# range_cape.net
KiCad netlist of a schematic drawn in EAGLE
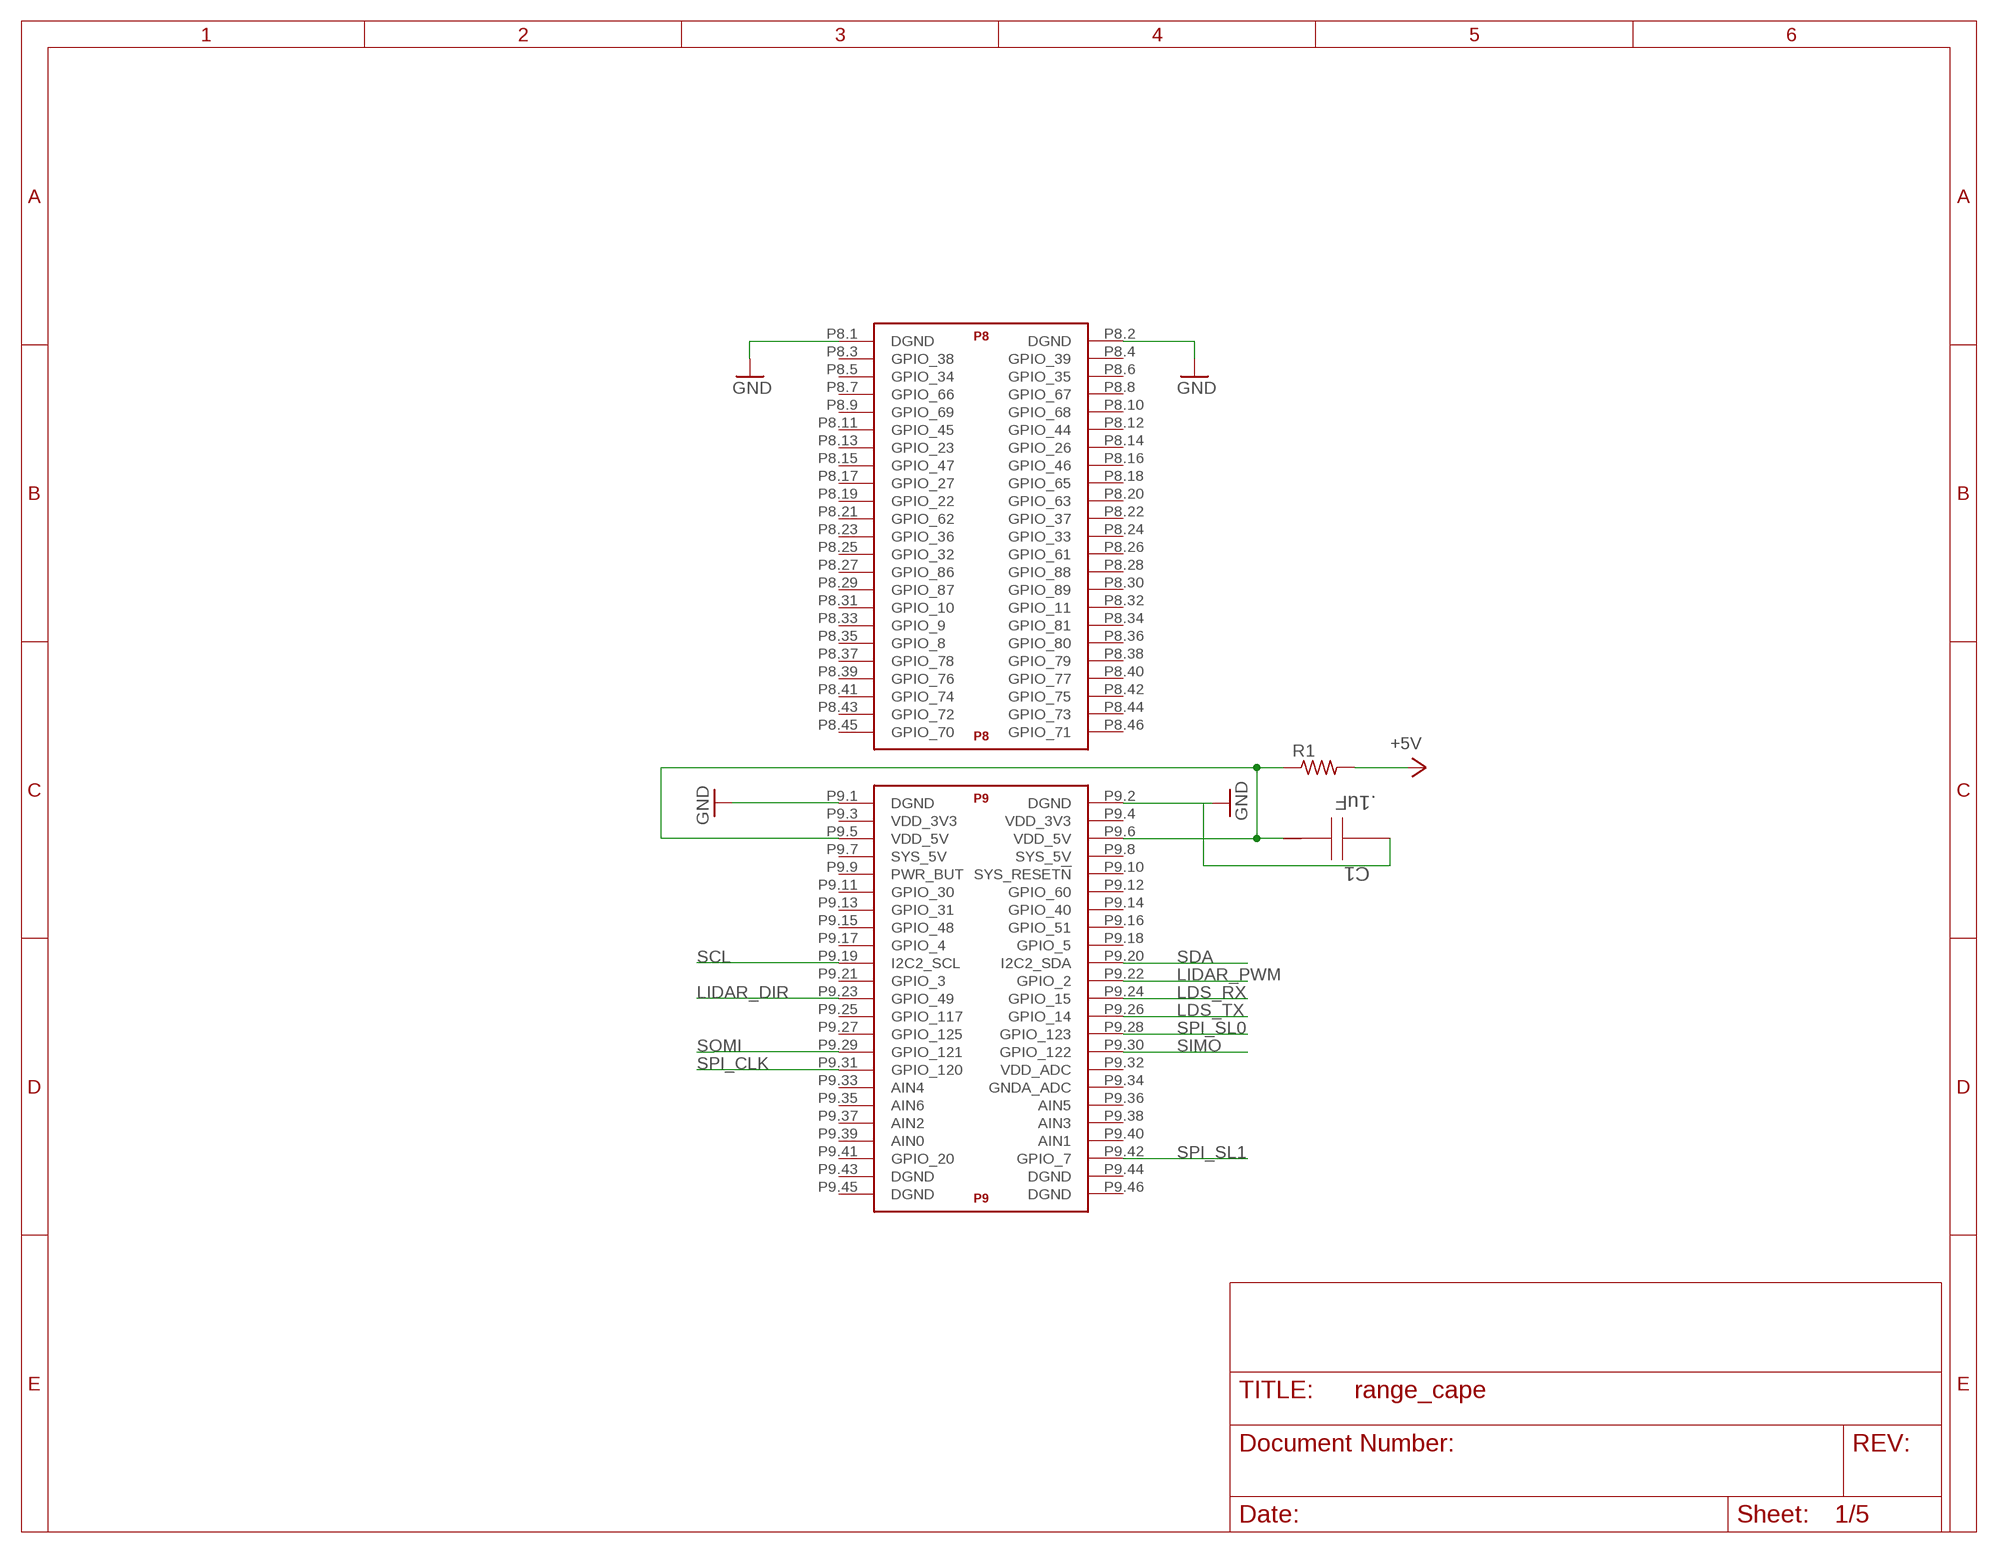
[diagram p0: schematic, sheet 1]
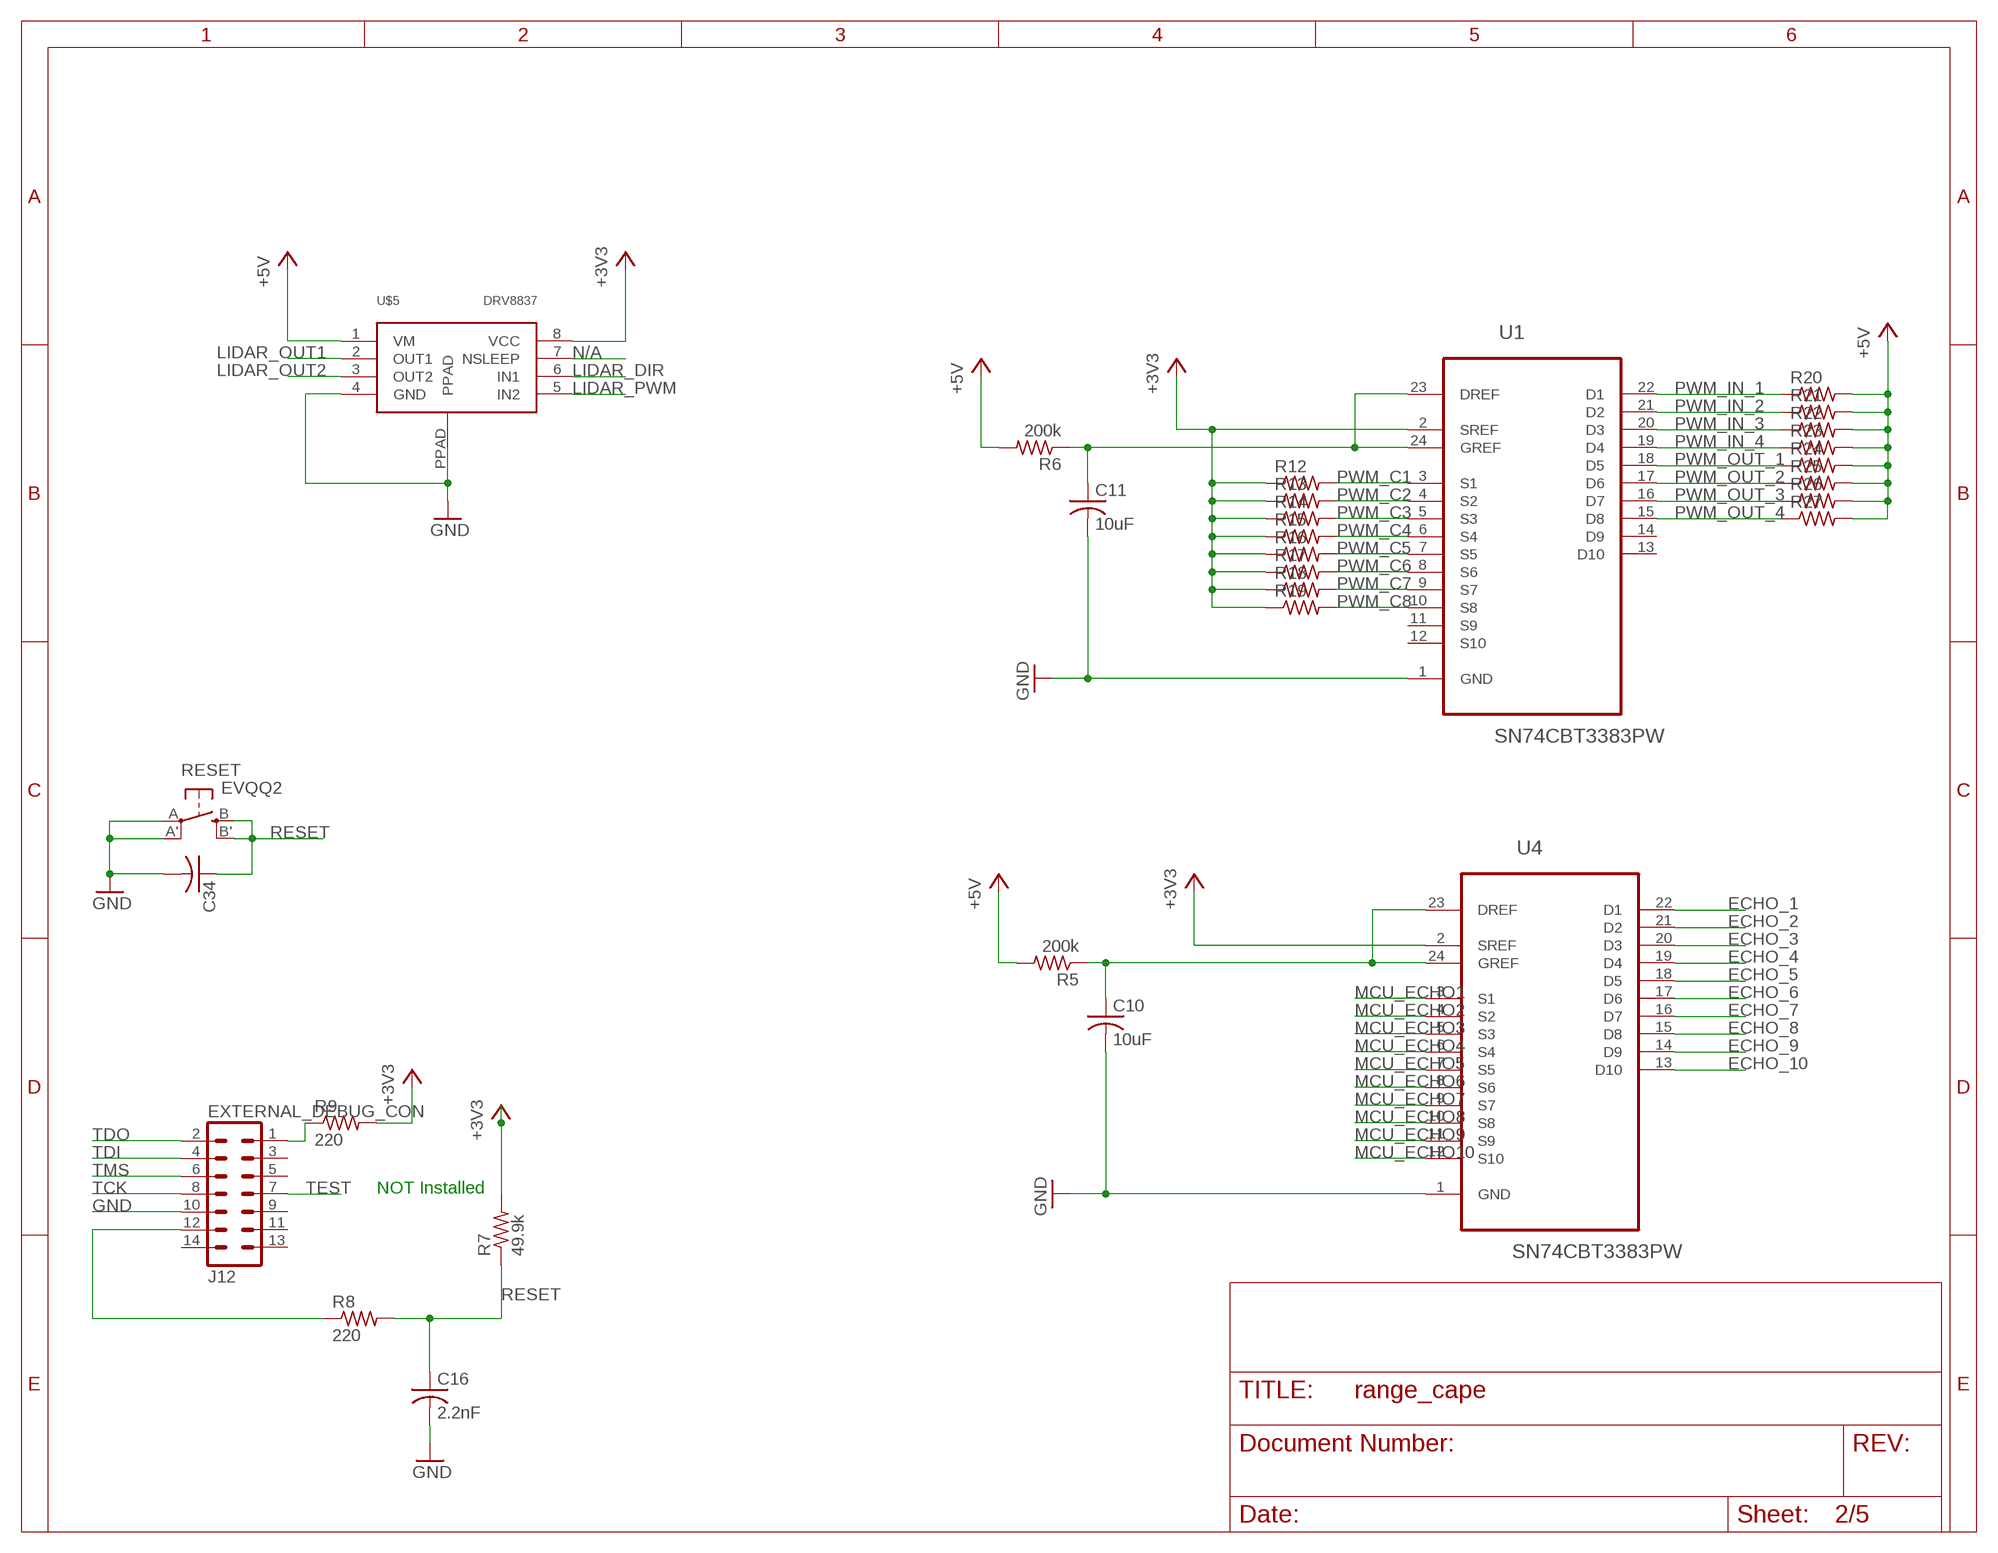
[diagram p1: schematic, sheet 2]
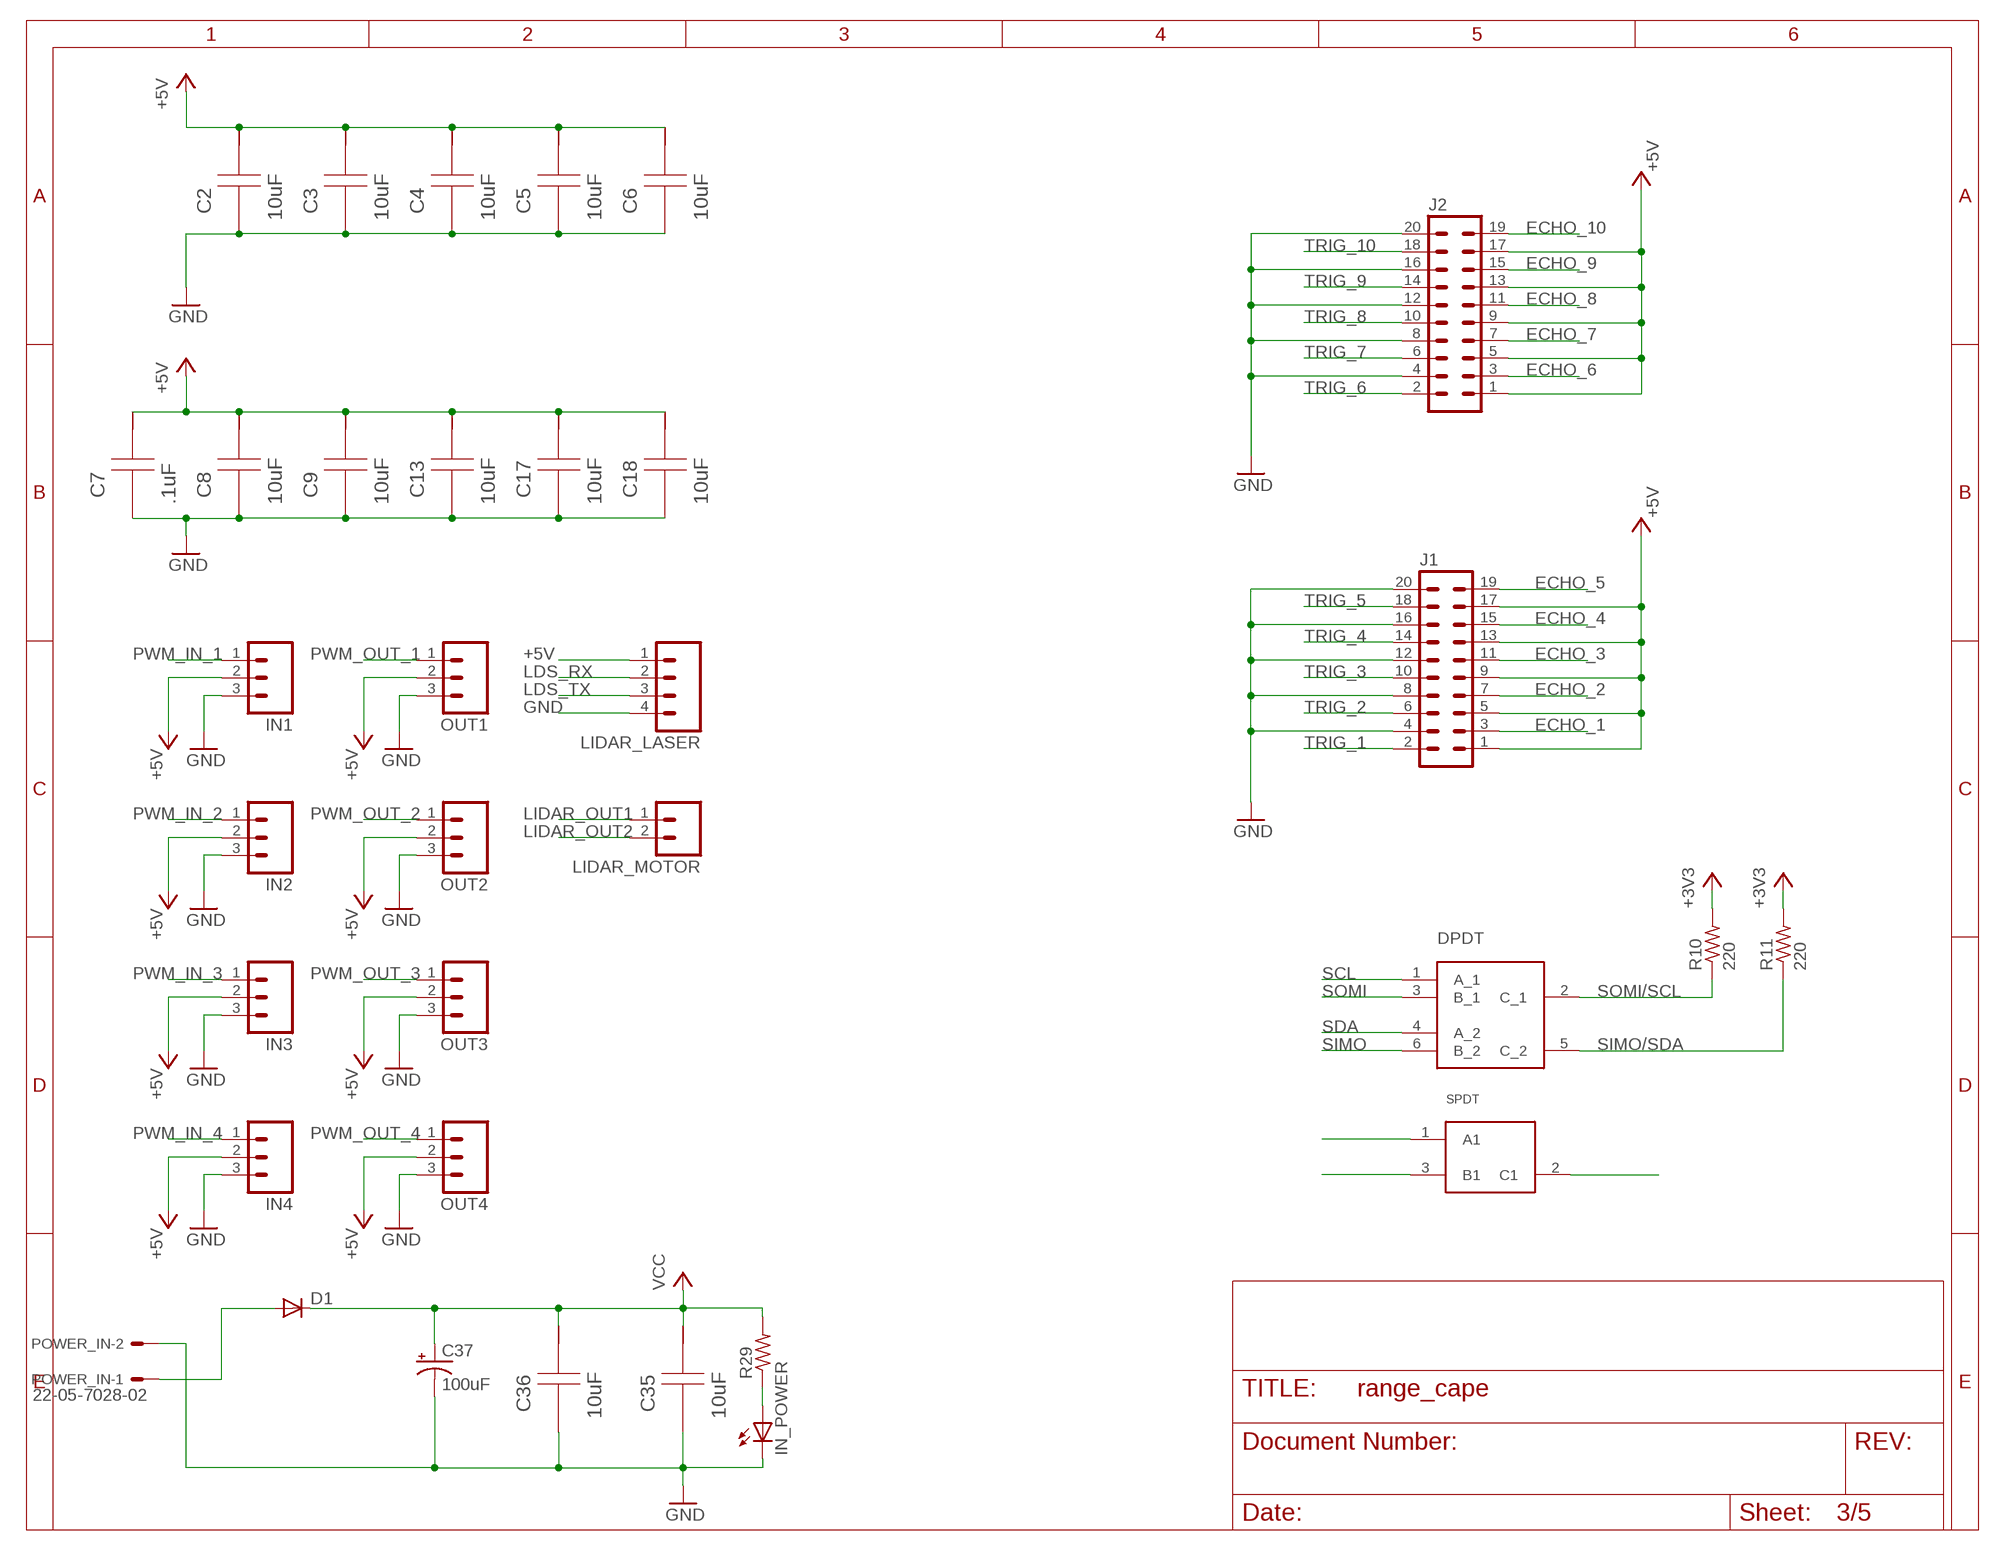
[diagram p2: schematic, sheet 3]
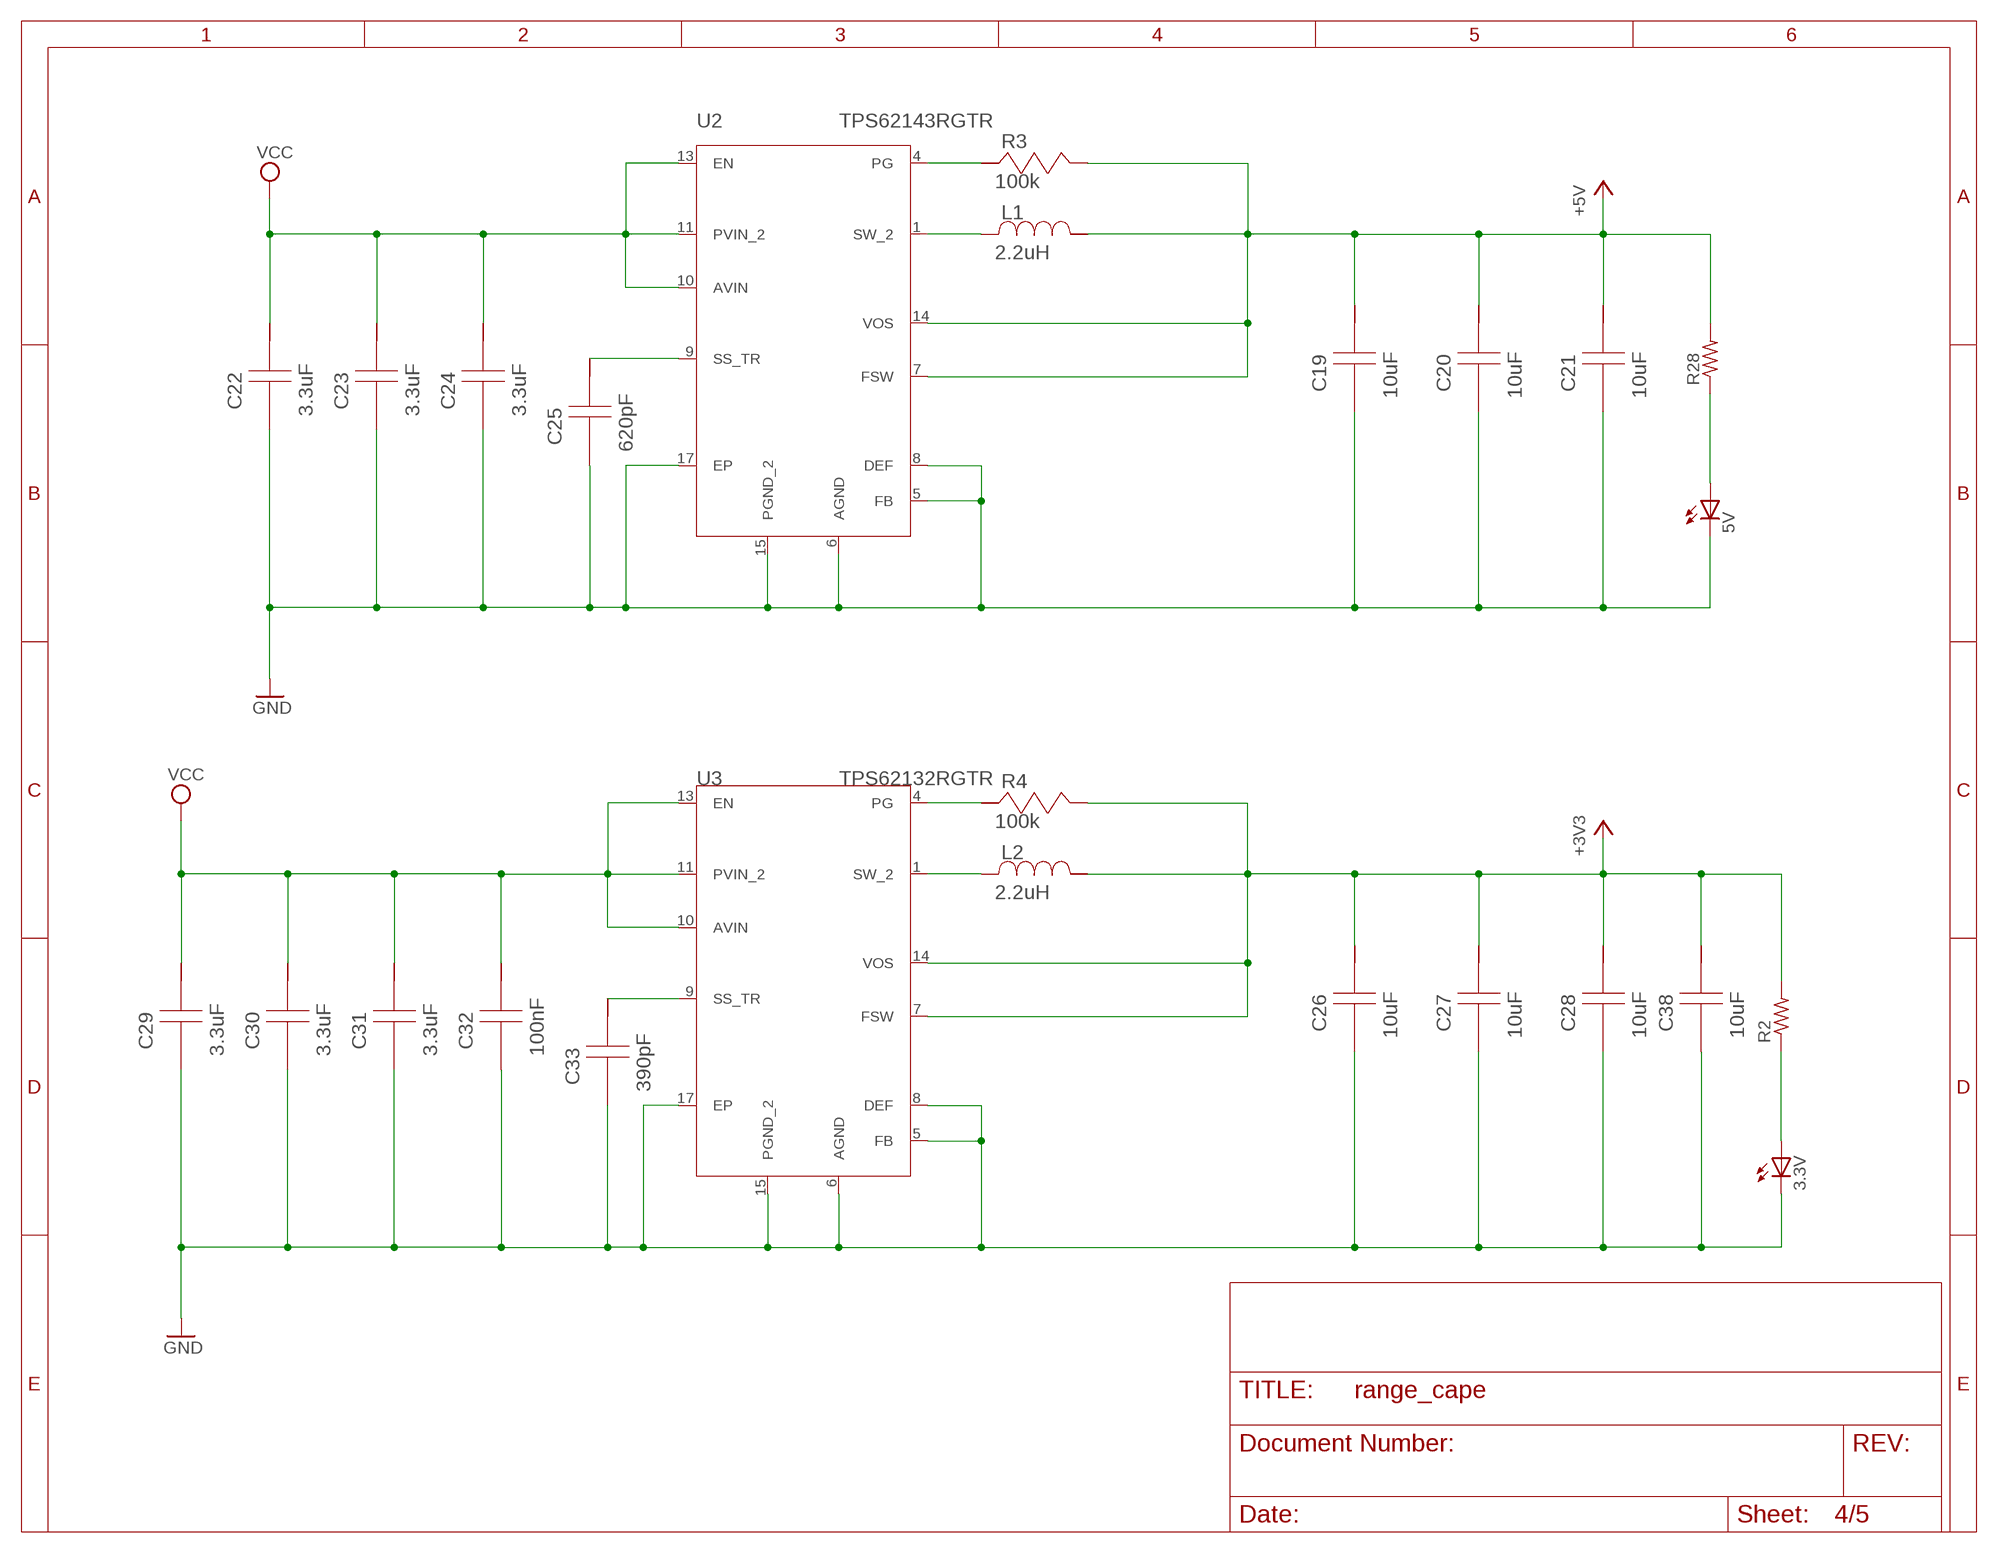
[diagram p3: schematic, sheet 4]
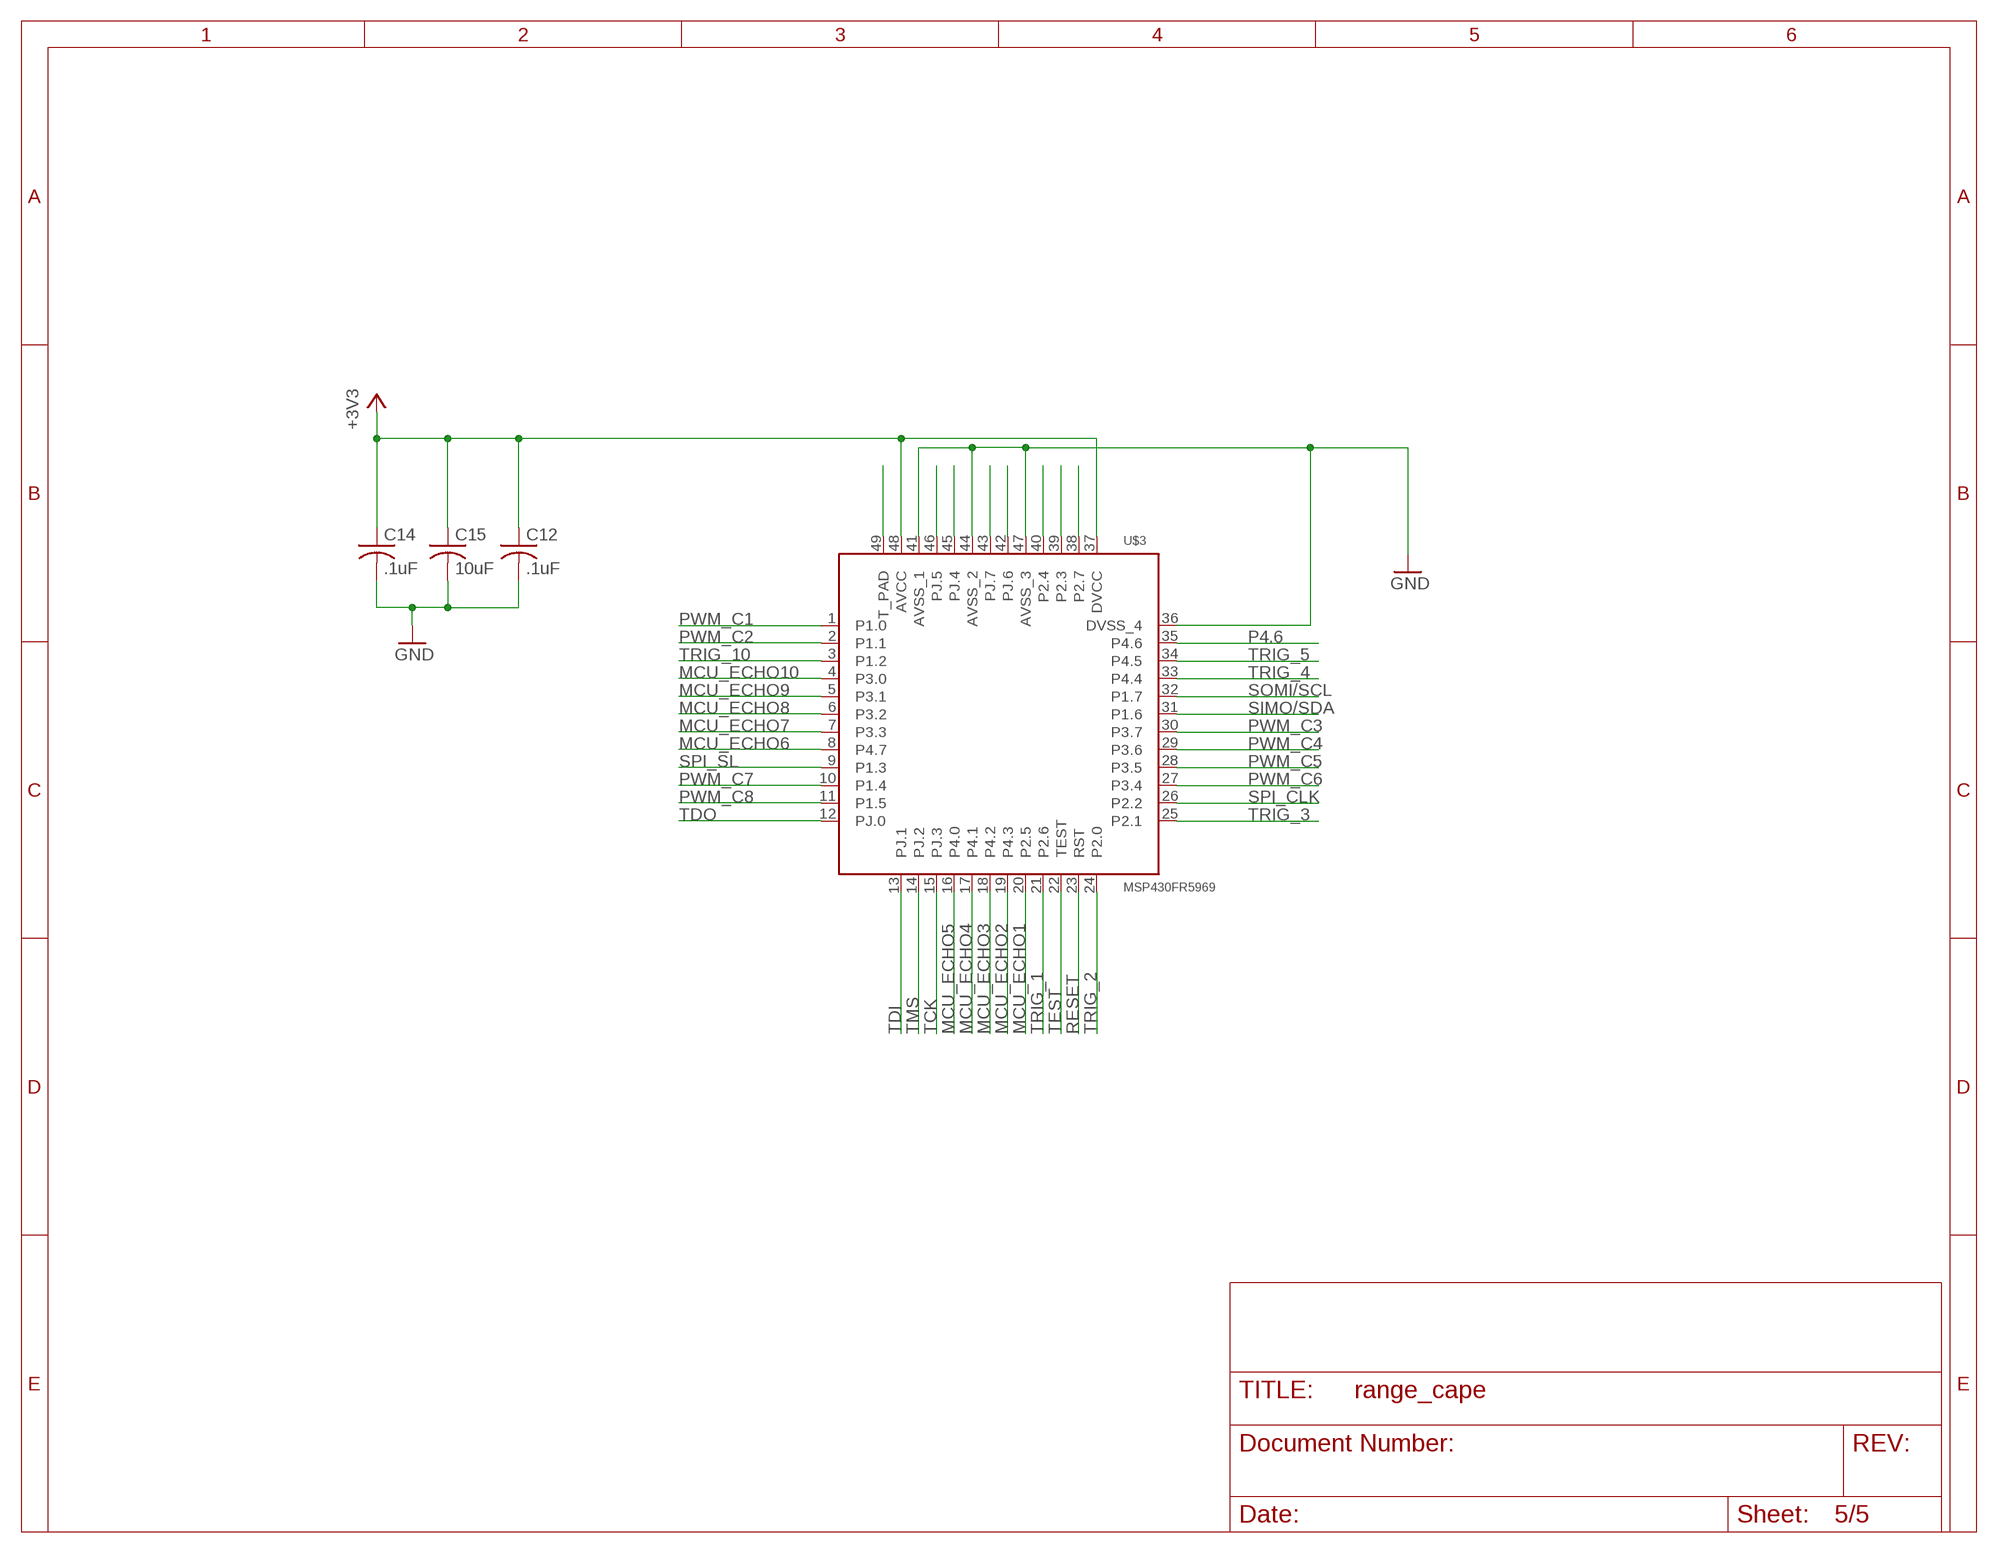
[diagram p4: schematic, sheet 5]

(export (version "E")
  (design (tool "Eeschema 10.0.6"))
  (components
    (comp (ref "C1")
      (value ".1uF")
      (footprint "eagle-import:1206")
      (fields (field (name "MANUFACTURER_PART_NUMBER") "C3216X5R1A106K"))
      (libsource (lib "eagle-import") (part "C3216X5R1A106K"))
    )
    (comp (ref "R1")
      (value "R-US_R1206")
      (footprint "eagle-import:R1206")
      (libsource (lib "eagle-import") (part "R-US_R1206"))
    )
    (comp (ref "U$1")
      (value "BEAGLE_BONE_BLACK_CAPE")
      (footprint "eagle-import:BEAGLE_BONE_BLACK_CAPE")
      (libsource (lib "eagle-import") (part "BEAGLE_BONE_BLACK_CAPE"))
    )
    (comp (ref "C10")
      (value "10uF")
      (footprint "eagle-import:C0805")
      (libsource (lib "eagle-import") (part "C-USC0805"))
    )
    (comp (ref "C11")
      (value "10uF")
      (footprint "eagle-import:C0805")
      (libsource (lib "eagle-import") (part "C-USC0805"))
    )
    (comp (ref "C16")
      (value "2.2nF")
      (footprint "eagle-import:C0603")
      (libsource (lib "eagle-import") (part "C-USC0603"))
    )
    (comp (ref "C34")
      (value "C-USC1206")
      (footprint "eagle-import:C1206")
      (libsource (lib "eagle-import") (part "C-USC1206"))
    )
    (comp (ref "J12")
      (value "EXTERNAL_DEBUG_CON")
      (footprint "eagle-import:EXTERNAL_DEBUG")
      (libsource (lib "eagle-import") (part "EXTERNAL_DEBUG_CON"))
    )
    (comp (ref "R5")
      (value "200k")
      (footprint "eagle-import:R0603")
      (libsource (lib "eagle-import") (part "R-US_R0603"))
    )
    (comp (ref "R6")
      (value "200k")
      (footprint "eagle-import:R0603")
      (libsource (lib "eagle-import") (part "R-US_R0603"))
    )
    (comp (ref "R7")
      (value "49.9k")
      (footprint "eagle-import:R0603")
      (libsource (lib "eagle-import") (part "R-US_R0603"))
    )
    (comp (ref "R8")
      (value "220")
      (footprint "eagle-import:R0603")
      (libsource (lib "eagle-import") (part "R-US_R0603"))
    )
    (comp (ref "R9")
      (value "220")
      (footprint "eagle-import:R0603")
      (libsource (lib "eagle-import") (part "R-US_R0603"))
    )
    (comp (ref "R12")
      (value "R-US_R0402")
      (footprint "eagle-import:R0402")
      (libsource (lib "eagle-import") (part "R-US_R0402"))
    )
    (comp (ref "R13")
      (value "R-US_R0402")
      (footprint "eagle-import:R0402")
      (libsource (lib "eagle-import") (part "R-US_R0402"))
    )
    (comp (ref "R14")
      (value "R-US_R0402")
      (footprint "eagle-import:R0402")
      (libsource (lib "eagle-import") (part "R-US_R0402"))
    )
    (comp (ref "R15")
      (value "R-US_R0402")
      (footprint "eagle-import:R0402")
      (libsource (lib "eagle-import") (part "R-US_R0402"))
    )
    (comp (ref "R16")
      (value "R-US_R0402")
      (footprint "eagle-import:R0402")
      (libsource (lib "eagle-import") (part "R-US_R0402"))
    )
    (comp (ref "R17")
      (value "R-US_R0402")
      (footprint "eagle-import:R0402")
      (libsource (lib "eagle-import") (part "R-US_R0402"))
    )
    (comp (ref "R18")
      (value "R-US_R0402")
      (footprint "eagle-import:R0402")
      (libsource (lib "eagle-import") (part "R-US_R0402"))
    )
    (comp (ref "R19")
      (value "R-US_R0402")
      (footprint "eagle-import:R0402")
      (libsource (lib "eagle-import") (part "R-US_R0402"))
    )
    (comp (ref "R20")
      (value "R-US_R0402")
      (footprint "eagle-import:R0402")
      (libsource (lib "eagle-import") (part "R-US_R0402"))
    )
    (comp (ref "R21")
      (value "R-US_R0402")
      (footprint "eagle-import:R0402")
      (libsource (lib "eagle-import") (part "R-US_R0402"))
    )
    (comp (ref "R22")
      (value "R-US_R0402")
      (footprint "eagle-import:R0402")
      (libsource (lib "eagle-import") (part "R-US_R0402"))
    )
    (comp (ref "R23")
      (value "R-US_R0402")
      (footprint "eagle-import:R0402")
      (libsource (lib "eagle-import") (part "R-US_R0402"))
    )
    (comp (ref "R24")
      (value "R-US_R0402")
      (footprint "eagle-import:R0402")
      (libsource (lib "eagle-import") (part "R-US_R0402"))
    )
    (comp (ref "R25")
      (value "R-US_R0402")
      (footprint "eagle-import:R0402")
      (libsource (lib "eagle-import") (part "R-US_R0402"))
    )
    (comp (ref "R26")
      (value "R-US_R0402")
      (footprint "eagle-import:R0402")
      (libsource (lib "eagle-import") (part "R-US_R0402"))
    )
    (comp (ref "R27")
      (value "R-US_R0402")
      (footprint "eagle-import:R0402")
      (libsource (lib "eagle-import") (part "R-US_R0402"))
    )
    (comp (ref "RESET")
      (value "EVQQ2")
      (footprint "eagle-import:EVQ-Q2")
      (libsource (lib "eagle-import") (part "EVQQ2"))
    )
    (comp (ref "U$5")
      (value "DRV8837")
      (footprint "eagle-import:WSON-8")
      (libsource (lib "eagle-import") (part "DRV8837"))
    )
    (comp (ref "U1")
      (value "SN74CBT3383PW")
      (footprint "eagle-import:SOP65P640X120-24N")
      (libsource (lib "eagle-import") (part "SN74CBT3383PW"))
    )
    (comp (ref "U4")
      (value "SN74CBT3383PW")
      (footprint "eagle-import:SOP65P640X120-24N")
      (libsource (lib "eagle-import") (part "SN74CBT3383PW"))
    )
    (comp (ref "C12")
      (value ".1uF")
      (footprint "eagle-import:C0805")
      (libsource (lib "eagle-import") (part "C-USC0805"))
    )
    (comp (ref "C14")
      (value ".1uF")
      (footprint "eagle-import:C0805")
      (libsource (lib "eagle-import") (part "C-USC0805"))
    )
    (comp (ref "C15")
      (value "10uF")
      (footprint "eagle-import:C0805")
      (libsource (lib "eagle-import") (part "C-USC0805"))
    )
    (comp (ref "U$3")
      (value "MSP430FR5969")
      (footprint "eagle-import:QFN50P700X700X100-49N")
      (libsource (lib "eagle-import") (part "MSP430FR5969"))
    )
    (comp (ref "C2")
      (value "10uF")
      (footprint "eagle-import:1206")
      (fields (field (name "MANUFACTURER_PART_NUMBER") "C3216X5R1A106K"))
      (libsource (lib "eagle-import") (part "C3216X5R1A106K"))
    )
    (comp (ref "C3")
      (value "10uF")
      (footprint "eagle-import:1206")
      (fields (field (name "MANUFACTURER_PART_NUMBER") "C3216X5R1A106K"))
      (libsource (lib "eagle-import") (part "C3216X5R1A106K"))
    )
    (comp (ref "C4")
      (value "10uF")
      (footprint "eagle-import:1206")
      (fields (field (name "MANUFACTURER_PART_NUMBER") "C3216X5R1A106K"))
      (libsource (lib "eagle-import") (part "C3216X5R1A106K"))
    )
    (comp (ref "C5")
      (value "10uF")
      (footprint "eagle-import:1206")
      (fields (field (name "MANUFACTURER_PART_NUMBER") "C3216X5R1A106K"))
      (libsource (lib "eagle-import") (part "C3216X5R1A106K"))
    )
    (comp (ref "C6")
      (value "10uF")
      (footprint "eagle-import:1206")
      (fields (field (name "MANUFACTURER_PART_NUMBER") "C3216X5R1A106K"))
      (libsource (lib "eagle-import") (part "C3216X5R1A106K"))
    )
    (comp (ref "C7")
      (value ".1uF")
      (footprint "eagle-import:1206")
      (fields (field (name "MANUFACTURER_PART_NUMBER") "C3216X5R1A106K"))
      (libsource (lib "eagle-import") (part "C3216X5R1A106K"))
    )
    (comp (ref "C8")
      (value "10uF")
      (footprint "eagle-import:1206")
      (fields (field (name "MANUFACTURER_PART_NUMBER") "C3216X5R1A106K"))
      (libsource (lib "eagle-import") (part "C3216X5R1A106K"))
    )
    (comp (ref "C9")
      (value "10uF")
      (footprint "eagle-import:1206")
      (fields (field (name "MANUFACTURER_PART_NUMBER") "C3216X5R1A106K"))
      (libsource (lib "eagle-import") (part "C3216X5R1A106K"))
    )
    (comp (ref "C13")
      (value "10uF")
      (footprint "eagle-import:1206")
      (fields (field (name "MANUFACTURER_PART_NUMBER") "C3216X5R1A106K"))
      (libsource (lib "eagle-import") (part "C3216X5R1A106K"))
    )
    (comp (ref "C17")
      (value "10uF")
      (footprint "eagle-import:1206")
      (fields (field (name "MANUFACTURER_PART_NUMBER") "C3216X5R1A106K"))
      (libsource (lib "eagle-import") (part "C3216X5R1A106K"))
    )
    (comp (ref "C18")
      (value "10uF")
      (footprint "eagle-import:1206")
      (fields (field (name "MANUFACTURER_PART_NUMBER") "C3216X5R1A106K"))
      (libsource (lib "eagle-import") (part "C3216X5R1A106K"))
    )
    (comp (ref "C35")
      (value "10uF")
      (footprint "eagle-import:1206")
      (fields (field (name "MANUFACTURER_PART_NUMBER") "C3216X5R1A106K"))
      (libsource (lib "eagle-import") (part "C3216X5R1A106K"))
    )
    (comp (ref "C36")
      (value "10uF")
      (footprint "eagle-import:1206")
      (fields (field (name "MANUFACTURER_PART_NUMBER") "C3216X5R1A106K"))
      (libsource (lib "eagle-import") (part "C3216X5R1A106K"))
    )
    (comp (ref "C37")
      (value "100uF")
      (footprint "eagle-import:EIA7343")
      (libsource (lib "eagle-import") (part "100UF-10V-10%(TANT)"))
    )
    (comp (ref "D1")
      (value "DIODE-DO-214AC")
      (footprint "eagle-import:DO-214AC")
      (libsource (lib "eagle-import") (part "DIODE-DO-214AC"))
    )
    (comp (ref "IN1")
      (value "M03LOCK")
      (footprint "eagle-import:1X03_LOCK")
      (libsource (lib "eagle-import") (part "M03LOCK"))
    )
    (comp (ref "IN2")
      (value "M03LOCK")
      (footprint "eagle-import:1X03_LOCK")
      (libsource (lib "eagle-import") (part "M03LOCK"))
    )
    (comp (ref "IN3")
      (value "M03LOCK")
      (footprint "eagle-import:1X03_LOCK")
      (libsource (lib "eagle-import") (part "M03LOCK"))
    )
    (comp (ref "IN4")
      (value "M03LOCK")
      (footprint "eagle-import:1X03_LOCK")
      (libsource (lib "eagle-import") (part "M03LOCK"))
    )
    (comp (ref "IN_POWER")
      (value "LED_ESML0603")
      (footprint "eagle-import:LED_SML0603")
      (libsource (lib "eagle-import") (part "LED_ESML0603"))
    )
    (comp (ref "J1")
      (value "MA10-2")
      (footprint "eagle-import:MA10-2")
      (libsource (lib "eagle-import") (part "MA10-2"))
    )
    (comp (ref "J2")
      (value "MA10-2")
      (footprint "eagle-import:MA10-2")
      (libsource (lib "eagle-import") (part "MA10-2"))
    )
    (comp (ref "LIDAR_LASER")
      (value "M04JST-PTH-VERT")
      (footprint "eagle-import:JST-4-PTH-VERT")
      (libsource (lib "eagle-import") (part "M04JST-PTH-VERT"))
    )
    (comp (ref "LIDAR_MOTOR")
      (value "M02JST-PTH-VERT")
      (footprint "eagle-import:JST-2-PTH-VERT")
      (libsource (lib "eagle-import") (part "M02JST-PTH-VERT"))
    )
    (comp (ref "OUT1")
      (value "M03LOCK")
      (footprint "eagle-import:1X03_LOCK")
      (libsource (lib "eagle-import") (part "M03LOCK"))
    )
    (comp (ref "OUT2")
      (value "M03LOCK")
      (footprint "eagle-import:1X03_LOCK")
      (libsource (lib "eagle-import") (part "M03LOCK"))
    )
    (comp (ref "OUT3")
      (value "M03LOCK")
      (footprint "eagle-import:1X03_LOCK")
      (libsource (lib "eagle-import") (part "M03LOCK"))
    )
    (comp (ref "OUT4")
      (value "M03LOCK")
      (footprint "eagle-import:1X03_LOCK")
      (libsource (lib "eagle-import") (part "M03LOCK"))
    )
    (comp (ref "POWER_IN")
      (value "22-05-7028-02")
      (footprint "eagle-import:7395-02")
      (libsource (lib "eagle-import") (part "22-?-0205-7028"))
    )
    (comp (ref "R10")
      (value "220")
      (footprint "eagle-import:R0402")
      (libsource (lib "eagle-import") (part "R-US_R0402"))
    )
    (comp (ref "R11")
      (value "220")
      (footprint "eagle-import:R0402")
      (libsource (lib "eagle-import") (part "R-US_R0402"))
    )
    (comp (ref "R29")
      (value "R-US_R0603")
      (footprint "eagle-import:R0603")
      (libsource (lib "eagle-import") (part "R-US_R0603"))
    )
    (comp (ref "SPDT")
      (value "SPDT_SWITCH")
      (footprint "eagle-import:SPDT")
      (libsource (lib "eagle-import") (part "SPDT_SWITCH"))
    )
    (comp (ref "U$4")
      (value "DPDT_I2C_SPI")
      (footprint "eagle-import:DPDT")
      (libsource (lib "eagle-import") (part "DPDT_I2C_SPI"))
    )
    (comp (ref "3.3V")
      (value "LED_ESML0603")
      (footprint "eagle-import:LED_SML0603")
      (libsource (lib "eagle-import") (part "LED_ESML0603"))
    )
    (comp (ref "5V")
      (value "LED_ESML0603")
      (footprint "eagle-import:LED_SML0603")
      (libsource (lib "eagle-import") (part "LED_ESML0603"))
    )
    (comp (ref "C19")
      (value "10uF")
      (footprint "eagle-import:1206")
      (fields (field (name "MANUFACTURER_PART_NUMBER") "C3216X5R1A106K"))
      (libsource (lib "eagle-import") (part "5v_fixed_C3216X5R1A106K"))
    )
    (comp (ref "C20")
      (value "10uF")
      (footprint "eagle-import:1206")
      (fields (field (name "MANUFACTURER_PART_NUMBER") "C3216X5R1A106K"))
      (libsource (lib "eagle-import") (part "5v_fixed_C3216X5R1A106K"))
    )
    (comp (ref "C21")
      (value "10uF")
      (footprint "eagle-import:1206")
      (fields (field (name "MANUFACTURER_PART_NUMBER") "C3216X5R1A106K"))
      (libsource (lib "eagle-import") (part "5v_fixed_C3216X5R1A106K"))
    )
    (comp (ref "C22")
      (value "3.3uF")
      (footprint "eagle-import:C3216X7R1E335K")
      (fields (field (name "MANUFACTURER_PART_NUMBER") "C3216X7R1E335K"))
      (libsource (lib "eagle-import") (part "C3216X7R1E335K"))
    )
    (comp (ref "C23")
      (value "3.3uF")
      (footprint "eagle-import:C3216X7R1E335K")
      (fields (field (name "MANUFACTURER_PART_NUMBER") "C3216X7R1E335K"))
      (libsource (lib "eagle-import") (part "C3216X7R1E335K"))
    )
    (comp (ref "C24")
      (value "3.3uF")
      (footprint "eagle-import:C3216X7R1E335K")
      (fields (field (name "MANUFACTURER_PART_NUMBER") "C3216X7R1E335K"))
      (libsource (lib "eagle-import") (part "C3216X7R1E335K"))
    )
    (comp (ref "C25")
      (value "620pF")
      (footprint "eagle-import:0402")
      (fields (field (name "MANUFACTURER_PART_NUMBER") "GRM1555C1E621JA01D"))
      (libsource (lib "eagle-import") (part "GRM1555C1E621JA01D"))
    )
    (comp (ref "C26")
      (value "10uF")
      (footprint "eagle-import:1206")
      (fields (field (name "MANUFACTURER_PART_NUMBER") "C3216X5R1A106K"))
      (libsource (lib "eagle-import") (part "5v_fixed_C3216X5R1A106K"))
    )
    (comp (ref "C27")
      (value "10uF")
      (footprint "eagle-import:1206")
      (fields (field (name "MANUFACTURER_PART_NUMBER") "C3216X5R1A106K"))
      (libsource (lib "eagle-import") (part "5v_fixed_C3216X5R1A106K"))
    )
    (comp (ref "C28")
      (value "10uF")
      (footprint "eagle-import:1206")
      (fields (field (name "MANUFACTURER_PART_NUMBER") "C3216X5R1A106K"))
      (libsource (lib "eagle-import") (part "5v_fixed_C3216X5R1A106K"))
    )
    (comp (ref "C29")
      (value "3.3uF")
      (footprint "eagle-import:C3216X7R1E335K")
      (fields (field (name "MANUFACTURER_PART_NUMBER") "C3216X7R1E335K"))
      (libsource (lib "eagle-import") (part "C3216X7R1E335K"))
    )
    (comp (ref "C30")
      (value "3.3uF")
      (footprint "eagle-import:C3216X7R1E335K")
      (fields (field (name "MANUFACTURER_PART_NUMBER") "C3216X7R1E335K"))
      (libsource (lib "eagle-import") (part "C3216X7R1E335K"))
    )
    (comp (ref "C31")
      (value "3.3uF")
      (footprint "eagle-import:C3216X7R1E335K")
      (fields (field (name "MANUFACTURER_PART_NUMBER") "C3216X7R1E335K"))
      (libsource (lib "eagle-import") (part "C3216X7R1E335K"))
    )
    (comp (ref "C32")
      (value "100nF")
      (footprint "eagle-import:0603")
      (fields (field (name "MANUFACTURER_PART_NUMBER") "C0603C104K3RACTU"))
      (libsource (lib "eagle-import") (part "C0603C104K3RACTU"))
    )
    (comp (ref "C33")
      (value "390pF")
      (footprint "eagle-import:0805")
      (fields (field (name "MANUFACTURER_PART_NUMBER") "08055C391KAT2A"))
      (libsource (lib "eagle-import") (part "08055C391KAT2A"))
    )
    (comp (ref "C38")
      (value "10uF")
      (footprint "eagle-import:1206")
      (fields (field (name "MANUFACTURER_PART_NUMBER") "C3216X5R1A106K"))
      (libsource (lib "eagle-import") (part "5v_fixed_C3216X5R1A106K"))
    )
    (comp (ref "L1")
      (value "2.2uH")
      (footprint "eagle-import:IHLP-1212BZ")
      (fields
        (field (name "MANUFACTURER") "Vishay")
        (field (name "MANUFACTURER_PART_NUMBER") "IHLP1212BZER2R2M11")
      )
      (libsource (lib "eagle-import") (part "IHLP1212BZER2R2M11"))
    )
    (comp (ref "L2")
      (value "2.2uH")
      (footprint "eagle-import:IHLP-1212BZ")
      (fields
        (field (name "MANUFACTURER") "Vishay")
        (field (name "MANUFACTURER_PART_NUMBER") "IHLP1212BZER2R2M11")
      )
      (libsource (lib "eagle-import") (part "IHLP1212BZER2R2M11"))
    )
    (comp (ref "R2")
      (value "R-US_R0603")
      (footprint "eagle-import:R0603")
      (libsource (lib "eagle-import") (part "R-US_R0603"))
    )
    (comp (ref "R3")
      (value "100k")
      (footprint "eagle-import:CRCW0402100KFKED")
      (fields
        (field (name "MANUFACTURER_PART_NUMBER") "CRCW0402100KFKED")
        (field (name "POWER") "0.063")
        (field (name "TOLERANCE") "1.0")
      )
      (libsource (lib "eagle-import") (part "CRCW0402100KFKED"))
    )
    (comp (ref "R4")
      (value "100k")
      (footprint "eagle-import:CRCW0402100KFKED")
      (fields
        (field (name "MANUFACTURER_PART_NUMBER") "CRCW0402100KFKED")
        (field (name "POWER") "0.063")
        (field (name "TOLERANCE") "1.0")
      )
      (libsource (lib "eagle-import") (part "CRCW0402100KFKED"))
    )
    (comp (ref "R28")
      (value "R-US_R0603")
      (footprint "eagle-import:R0603")
      (libsource (lib "eagle-import") (part "R-US_R0603"))
    )
    (comp (ref "U2")
      (value "TPS62143RGTR")
      (footprint "eagle-import:S-PVQFN-N16")
      (fields (field (name "MANUFACTURER_PART_NUMBER") "TPS62131RGTR"))
      (libsource (lib "eagle-import") (part "TPS62143RGTR"))
    )
    (comp (ref "U3")
      (value "TPS62132RGTR")
      (footprint "eagle-import:S-PVQFN-N16")
      (fields (field (name "MANUFACTURER_PART_NUMBER") "TPS62131RGTR"))
      (libsource (lib "eagle-import") (part "TPS62132RGTR"))
    )
  )
  (nets
    (net (code "1") (name "+3V3") (class "Default")
      (node (ref "C12") (pin "1") (pinfunction "1_1") (pintype "passive"))
      (node (ref "C14") (pin "1") (pinfunction "1_1") (pintype "passive"))
      (node (ref "C15") (pin "1") (pinfunction "1_1") (pintype "passive"))
      (node (ref "C26") (pin "1") (pinfunction "1_1") (pintype "passive"))
      (node (ref "C27") (pin "1") (pinfunction "1_1") (pintype "passive"))
      (node (ref "C28") (pin "1") (pinfunction "1_1") (pintype "passive"))
      (node (ref "C38") (pin "1") (pinfunction "1_1") (pintype "passive"))
      (node (ref "L2") (pin "2") (pinfunction "2_2") (pintype "passive"))
      (node (ref "R10") (pin "2") (pinfunction "2_2") (pintype "passive"))
      (node (ref "R11") (pin "2") (pinfunction "2_2") (pintype "passive"))
      (node (ref "R12") (pin "1") (pinfunction "1_1") (pintype "passive"))
      (node (ref "R13") (pin "1") (pinfunction "1_1") (pintype "passive"))
      (node (ref "R14") (pin "1") (pinfunction "1_1") (pintype "passive"))
      (node (ref "R15") (pin "1") (pinfunction "1_1") (pintype "passive"))
      (node (ref "R16") (pin "1") (pinfunction "1_1") (pintype "passive"))
      (node (ref "R17") (pin "1") (pinfunction "1_1") (pintype "passive"))
      (node (ref "R18") (pin "1") (pinfunction "1_1") (pintype "passive"))
      (node (ref "R19") (pin "1") (pinfunction "1_1") (pintype "passive"))
      (node (ref "R2") (pin "2") (pinfunction "2_2") (pintype "passive"))
      (node (ref "R4") (pin "1") (pinfunction "1_1") (pintype "passive"))
      (node (ref "R7") (pin "2") (pinfunction "2_2") (pintype "passive"))
      (node (ref "R9") (pin "2") (pinfunction "2_2") (pintype "passive"))
      (node (ref "U$3") (pin "37") (pinfunction "DVCC_37") (pintype "power_in"))
      (node (ref "U$3") (pin "48") (pinfunction "AVCC_48") (pintype "power_in"))
      (node (ref "U$5") (pin "8") (pinfunction "VCC_8") (pintype "bidirectional"))
      (node (ref "U1") (pin "2") (pinfunction "SREF_2") (pintype "input"))
      (node (ref "U3") (pin "14") (pinfunction "VOS_14") (pintype "passive"))
      (node (ref "U3") (pin "7") (pinfunction "FSW_7") (pintype "passive"))
      (node (ref "U4") (pin "2") (pinfunction "SREF_2") (pintype "input"))
    )
    (net (code "2") (name "+5V") (class "Default")
      (node (ref "C13") (pin "1") (pinfunction "1_1") (pintype "passive"))
      (node (ref "C17") (pin "1") (pinfunction "1_1") (pintype "passive"))
      (node (ref "C18") (pin "1") (pinfunction "1_1") (pintype "passive"))
      (node (ref "C19") (pin "1") (pinfunction "1_1") (pintype "passive"))
      (node (ref "C2") (pin "1") (pinfunction "1_1") (pintype "passive"))
      (node (ref "C20") (pin "1") (pinfunction "1_1") (pintype "passive"))
      (node (ref "C21") (pin "1") (pinfunction "1_1") (pintype "passive"))
      (node (ref "C3") (pin "1") (pinfunction "1_1") (pintype "passive"))
      (node (ref "C4") (pin "1") (pinfunction "1_1") (pintype "passive"))
      (node (ref "C5") (pin "1") (pinfunction "1_1") (pintype "passive"))
      (node (ref "C6") (pin "1") (pinfunction "1_1") (pintype "passive"))
      (node (ref "C7") (pin "1") (pinfunction "1_1") (pintype "passive"))
      (node (ref "C8") (pin "1") (pinfunction "1_1") (pintype "passive"))
      (node (ref "C9") (pin "1") (pinfunction "1_1") (pintype "passive"))
      (node (ref "IN1") (pin "2") (pinfunction "2_2") (pintype "passive"))
      (node (ref "IN2") (pin "2") (pinfunction "2_2") (pintype "passive"))
      (node (ref "IN3") (pin "2") (pinfunction "2_2") (pintype "passive"))
      (node (ref "IN4") (pin "2") (pinfunction "2_2") (pintype "passive"))
      (node (ref "J1") (pin "1") (pinfunction "1_1") (pintype "passive"))
      (node (ref "J1") (pin "13") (pinfunction "13_13") (pintype "passive"))
      (node (ref "J1") (pin "17") (pinfunction "17_17") (pintype "passive"))
      (node (ref "J1") (pin "5") (pinfunction "5_5") (pintype "passive"))
      (node (ref "J1") (pin "9") (pinfunction "9_9") (pintype "passive"))
      (node (ref "J2") (pin "1") (pinfunction "1_1") (pintype "passive"))
      (node (ref "J2") (pin "13") (pinfunction "13_13") (pintype "passive"))
      (node (ref "J2") (pin "17") (pinfunction "17_17") (pintype "passive"))
      (node (ref "J2") (pin "5") (pinfunction "5_5") (pintype "passive"))
      (node (ref "J2") (pin "9") (pinfunction "9_9") (pintype "passive"))
      (node (ref "L1") (pin "2") (pinfunction "2_2") (pintype "passive"))
      (node (ref "LIDAR_LASER") (pin "1") (pinfunction "1_1") (pintype "passive"))
      (node (ref "OUT1") (pin "2") (pinfunction "2_2") (pintype "passive"))
      (node (ref "OUT2") (pin "2") (pinfunction "2_2") (pintype "passive"))
      (node (ref "OUT3") (pin "2") (pinfunction "2_2") (pintype "passive"))
      (node (ref "OUT4") (pin "2") (pinfunction "2_2") (pintype "passive"))
      (node (ref "R1") (pin "2") (pinfunction "2_2") (pintype "passive"))
      (node (ref "R20") (pin "2") (pinfunction "2_2") (pintype "passive"))
      (node (ref "R21") (pin "2") (pinfunction "2_2") (pintype "passive"))
      (node (ref "R22") (pin "2") (pinfunction "2_2") (pintype "passive"))
      (node (ref "R23") (pin "2") (pinfunction "2_2") (pintype "passive"))
      (node (ref "R24") (pin "2") (pinfunction "2_2") (pintype "passive"))
      (node (ref "R25") (pin "2") (pinfunction "2_2") (pintype "passive"))
      (node (ref "R26") (pin "2") (pinfunction "2_2") (pintype "passive"))
      (node (ref "R27") (pin "2") (pinfunction "2_2") (pintype "passive"))
      (node (ref "R28") (pin "2") (pinfunction "2_2") (pintype "passive"))
      (node (ref "R3") (pin "1") (pinfunction "1_1") (pintype "passive"))
      (node (ref "R5") (pin "2") (pinfunction "2_2") (pintype "passive"))
      (node (ref "R6") (pin "2") (pinfunction "2_2") (pintype "passive"))
      (node (ref "U$5") (pin "1") (pinfunction "VM_1") (pintype "bidirectional"))
      (node (ref "U2") (pin "14") (pinfunction "VOS_14") (pintype "passive"))
      (node (ref "U2") (pin "7") (pinfunction "FSW_7") (pintype "passive"))
    )
    (net (code "3") (name "ECHO_1") (class "Default")
      (node (ref "J1") (pin "3") (pinfunction "3_3") (pintype "passive"))
      (node (ref "U4") (pin "22") (pinfunction "D1_22") (pintype "bidirectional"))
    )
    (net (code "4") (name "ECHO_2") (class "Default")
      (node (ref "J1") (pin "7") (pinfunction "7_7") (pintype "passive"))
      (node (ref "U4") (pin "21") (pinfunction "D2_21") (pintype "bidirectional"))
    )
    (net (code "5") (name "ECHO_3") (class "Default")
      (node (ref "J1") (pin "11") (pinfunction "11_11") (pintype "passive"))
      (node (ref "U4") (pin "20") (pinfunction "D3_20") (pintype "bidirectional"))
    )
    (net (code "6") (name "ECHO_4") (class "Default")
      (node (ref "J1") (pin "15") (pinfunction "15_15") (pintype "passive"))
      (node (ref "U4") (pin "19") (pinfunction "D4_19") (pintype "bidirectional"))
    )
    (net (code "7") (name "ECHO_5") (class "Default")
      (node (ref "J1") (pin "19") (pinfunction "19_19") (pintype "passive"))
      (node (ref "U4") (pin "18") (pinfunction "D5_18") (pintype "bidirectional"))
    )
    (net (code "8") (name "ECHO_6") (class "Default")
      (node (ref "J2") (pin "3") (pinfunction "3_3") (pintype "passive"))
      (node (ref "U4") (pin "17") (pinfunction "D6_17") (pintype "bidirectional"))
    )
    (net (code "9") (name "ECHO_7") (class "Default")
      (node (ref "J2") (pin "7") (pinfunction "7_7") (pintype "passive"))
      (node (ref "U4") (pin "16") (pinfunction "D7_16") (pintype "bidirectional"))
    )
    (net (code "10") (name "ECHO_8") (class "Default")
      (node (ref "J2") (pin "11") (pinfunction "11_11") (pintype "passive"))
      (node (ref "U4") (pin "15") (pinfunction "D8_15") (pintype "bidirectional"))
    )
    (net (code "11") (name "ECHO_9") (class "Default")
      (node (ref "J2") (pin "15") (pinfunction "15_15") (pintype "passive"))
      (node (ref "U4") (pin "14") (pinfunction "D9_14") (pintype "bidirectional"))
    )
    (net (code "12") (name "ECHO_10") (class "Default")
      (node (ref "J2") (pin "19") (pinfunction "19_19") (pintype "passive"))
      (node (ref "U4") (pin "13") (pinfunction "D10_13") (pintype "bidirectional"))
    )
    (net (code "13") (name "GND") (class "Default")
      (node (ref "3.3V") (pin "C") (pinfunction "C_C") (pintype "passive"))
      (node (ref "5V") (pin "C") (pinfunction "C_C") (pintype "passive"))
      (node (ref "C1") (pin "2") (pinfunction "2_2") (pintype "passive"))
      (node (ref "C10") (pin "2") (pinfunction "2_2") (pintype "passive"))
      (node (ref "C11") (pin "2") (pinfunction "2_2") (pintype "passive"))
      (node (ref "C12") (pin "2") (pinfunction "2_2") (pintype "passive"))
      (node (ref "C13") (pin "2") (pinfunction "2_2") (pintype "passive"))
      (node (ref "C14") (pin "2") (pinfunction "2_2") (pintype "passive"))
      (node (ref "C15") (pin "2") (pinfunction "2_2") (pintype "passive"))
      (node (ref "C16") (pin "2") (pinfunction "2_2") (pintype "passive"))
      (node (ref "C17") (pin "2") (pinfunction "2_2") (pintype "passive"))
      (node (ref "C18") (pin "2") (pinfunction "2_2") (pintype "passive"))
      (node (ref "C19") (pin "2") (pinfunction "2_2") (pintype "passive"))
      (node (ref "C2") (pin "2") (pinfunction "2_2") (pintype "passive"))
      (node (ref "C20") (pin "2") (pinfunction "2_2") (pintype "passive"))
      (node (ref "C21") (pin "2") (pinfunction "2_2") (pintype "passive"))
      (node (ref "C22") (pin "2") (pinfunction "2_2") (pintype "passive"))
      (node (ref "C23") (pin "2") (pinfunction "2_2") (pintype "passive"))
      (node (ref "C24") (pin "2") (pinfunction "2_2") (pintype "passive"))
      (node (ref "C25") (pin "2") (pinfunction "2_2") (pintype "passive"))
      (node (ref "C26") (pin "2") (pinfunction "2_2") (pintype "passive"))
      (node (ref "C27") (pin "2") (pinfunction "2_2") (pintype "passive"))
      (node (ref "C28") (pin "2") (pinfunction "2_2") (pintype "passive"))
      (node (ref "C29") (pin "2") (pinfunction "2_2") (pintype "passive"))
      (node (ref "C3") (pin "2") (pinfunction "2_2") (pintype "passive"))
      (node (ref "C30") (pin "2") (pinfunction "2_2") (pintype "passive"))
      (node (ref "C31") (pin "2") (pinfunction "2_2") (pintype "passive"))
      (node (ref "C32") (pin "2") (pinfunction "2_2") (pintype "passive"))
      (node (ref "C33") (pin "2") (pinfunction "2_2") (pintype "passive"))
      (node (ref "C34") (pin "2") (pinfunction "2_2") (pintype "passive"))
      (node (ref "C35") (pin "2") (pinfunction "2_2") (pintype "passive"))
      (node (ref "C36") (pin "2") (pinfunction "2_2") (pintype "passive"))
      (node (ref "C37") (pin "C") (pinfunction "-_C") (pintype "passive"))
      (node (ref "C38") (pin "2") (pinfunction "2_2") (pintype "passive"))
      (node (ref "C4") (pin "2") (pinfunction "2_2") (pintype "passive"))
      (node (ref "C5") (pin "2") (pinfunction "2_2") (pintype "passive"))
      (node (ref "C6") (pin "2") (pinfunction "2_2") (pintype "passive"))
      (node (ref "C7") (pin "2") (pinfunction "2_2") (pintype "passive"))
      (node (ref "C8") (pin "2") (pinfunction "2_2") (pintype "passive"))
      (node (ref "C9") (pin "2") (pinfunction "2_2") (pintype "passive"))
      (node (ref "IN1") (pin "3") (pinfunction "3_3") (pintype "passive"))
      (node (ref "IN2") (pin "3") (pinfunction "3_3") (pintype "passive"))
      (node (ref "IN3") (pin "3") (pinfunction "3_3") (pintype "passive"))
      (node (ref "IN4") (pin "3") (pinfunction "3_3") (pintype "passive"))
      (node (ref "IN_POWER") (pin "C") (pinfunction "C_C") (pintype "passive"))
      (node (ref "J1") (pin "12") (pinfunction "12_12") (pintype "passive"))
      (node (ref "J1") (pin "16") (pinfunction "16_16") (pintype "passive"))
      (node (ref "J1") (pin "20") (pinfunction "20_20") (pintype "passive"))
      (node (ref "J1") (pin "4") (pinfunction "4_4") (pintype "passive"))
      (node (ref "J1") (pin "8") (pinfunction "8_8") (pintype "passive"))
      (node (ref "J12") (pin "10") (pinfunction "10_10") (pintype "passive"))
      (node (ref "J2") (pin "12") (pinfunction "12_12") (pintype "passive"))
      (node (ref "J2") (pin "16") (pinfunction "16_16") (pintype "passive"))
      (node (ref "J2") (pin "20") (pinfunction "20_20") (pintype "passive"))
      (node (ref "J2") (pin "4") (pinfunction "4_4") (pintype "passive"))
      (node (ref "J2") (pin "8") (pinfunction "8_8") (pintype "passive"))
      (node (ref "LIDAR_LASER") (pin "4") (pinfunction "4_4") (pintype "passive"))
      (node (ref "OUT1") (pin "3") (pinfunction "3_3") (pintype "passive"))
      (node (ref "OUT2") (pin "3") (pinfunction "3_3") (pintype "passive"))
      (node (ref "OUT3") (pin "3") (pinfunction "3_3") (pintype "passive"))
      (node (ref "OUT4") (pin "3") (pinfunction "3_3") (pintype "passive"))
      (node (ref "POWER_IN") (pin "2") (pinfunction "S_2") (pintype "passive"))
      (node (ref "RESET") (pin "A") (pinfunction "P_A") (pintype "passive"))
      (node (ref "RESET") (pin "A'") (pinfunction "P1_A'") (pintype "passive"))
      (node (ref "U$1") (pin "P8.1") (pinfunction "DGND_P8.1") (pintype "bidirectional"))
      (node (ref "U$1") (pin "P8.2") (pinfunction "DGND_P8.2") (pintype "bidirectional"))
      (node (ref "U$1") (pin "P9.1") (pinfunction "DGND_P9.1") (pintype "bidirectional"))
      (node (ref "U$1") (pin "P9.2") (pinfunction "DGND_P9.2") (pintype "bidirectional"))
      (node (ref "U$3") (pin "36") (pinfunction "DVSS_4_36") (pintype "power_in"))
      (node (ref "U$3") (pin "41") (pinfunction "AVSS_1_41") (pintype "power_in"))
      (node (ref "U$3") (pin "44") (pinfunction "AVSS_2_44") (pintype "power_in"))
      (node (ref "U$3") (pin "47") (pinfunction "AVSS_3_47") (pintype "power_in"))
      (node (ref "U$5") (pin "4") (pinfunction "GND_4") (pintype "bidirectional"))
      (node (ref "U$5") (pin "PPAD") (pinfunction "PPAD_PPAD") (pintype "bidirectional"))
      (node (ref "U1") (pin "1") (pinfunction "GND_1") (pintype "passive"))
      (node (ref "U2") (pin "15") (pinfunction "PGND_2_15") (pintype "passive"))
      (node (ref "U2") (pin "17") (pinfunction "EP_17") (pintype "passive"))
      (node (ref "U2") (pin "5") (pinfunction "FB_5") (pintype "passive"))
      (node (ref "U2") (pin "6") (pinfunction "AGND_6") (pintype "passive"))
      (node (ref "U2") (pin "8") (pinfunction "DEF_8") (pintype "passive"))
      (node (ref "U3") (pin "15") (pinfunction "PGND_2_15") (pintype "passive"))
      (node (ref "U3") (pin "17") (pinfunction "EP_17") (pintype "passive"))
      (node (ref "U3") (pin "5") (pinfunction "FB_5") (pintype "passive"))
      (node (ref "U3") (pin "6") (pinfunction "AGND_6") (pintype "passive"))
      (node (ref "U3") (pin "8") (pinfunction "DEF_8") (pintype "passive"))
      (node (ref "U4") (pin "1") (pinfunction "GND_1") (pintype "passive"))
    )
    (net (code "14") (name "LDS_RX") (class "Default")
      (node (ref "LIDAR_LASER") (pin "2") (pinfunction "2_2") (pintype "passive"))
      (node (ref "U$1") (pin "P9.24") (pinfunction "GPIO_15_P9.24") (pintype "bidirectional"))
    )
    (net (code "15") (name "LDS_TX") (class "Default")
      (node (ref "LIDAR_LASER") (pin "3") (pinfunction "3_3") (pintype "passive"))
      (node (ref "U$1") (pin "P9.26") (pinfunction "GPIO_14_P9.26") (pintype "bidirectional"))
    )
    (net (code "16") (name "LIDAR_DIR") (class "Default")
      (node (ref "U$1") (pin "P9.23") (pinfunction "GPIO_49_P9.23") (pintype "bidirectional"))
      (node (ref "U$5") (pin "6") (pinfunction "IN1_6") (pintype "bidirectional"))
    )
    (net (code "17") (name "LIDAR_OUT1") (class "Default")
      (node (ref "LIDAR_MOTOR") (pin "1") (pinfunction "1_1") (pintype "passive"))
      (node (ref "U$5") (pin "2") (pinfunction "OUT1_2") (pintype "bidirectional"))
    )
    (net (code "18") (name "LIDAR_OUT2") (class "Default")
      (node (ref "LIDAR_MOTOR") (pin "2") (pinfunction "2_2") (pintype "passive"))
      (node (ref "U$5") (pin "3") (pinfunction "OUT2_3") (pintype "bidirectional"))
    )
    (net (code "19") (name "LIDAR_PWM") (class "Default")
      (node (ref "U$1") (pin "P9.22") (pinfunction "GPIO_2_P9.22") (pintype "bidirectional"))
      (node (ref "U$5") (pin "5") (pinfunction "IN2_5") (pintype "bidirectional"))
    )
    (net (code "20") (name "MCU_ECHO1") (class "Default")
      (node (ref "U$3") (pin "20") (pinfunction "P2.5_20") (pintype "power_in"))
      (node (ref "U4") (pin "3") (pinfunction "S1_3") (pintype "bidirectional"))
    )
    (net (code "21") (name "MCU_ECHO2") (class "Default")
      (node (ref "U$3") (pin "19") (pinfunction "P4.3_19") (pintype "power_in"))
      (node (ref "U4") (pin "4") (pinfunction "S2_4") (pintype "bidirectional"))
    )
    (net (code "22") (name "MCU_ECHO3") (class "Default")
      (node (ref "U$3") (pin "18") (pinfunction "P4.2_18") (pintype "power_in"))
      (node (ref "U4") (pin "5") (pinfunction "S3_5") (pintype "bidirectional"))
    )
    (net (code "23") (name "MCU_ECHO4") (class "Default")
      (node (ref "U$3") (pin "17") (pinfunction "P4.1_17") (pintype "power_in"))
      (node (ref "U4") (pin "6") (pinfunction "S4_6") (pintype "bidirectional"))
    )
    (net (code "24") (name "MCU_ECHO5") (class "Default")
      (node (ref "U$3") (pin "16") (pinfunction "P4.0_16") (pintype "power_in"))
      (node (ref "U4") (pin "7") (pinfunction "S5_7") (pintype "bidirectional"))
    )
    (net (code "25") (name "MCU_ECHO6") (class "Default")
      (node (ref "U$3") (pin "8") (pinfunction "P4.7_8") (pintype "power_in"))
      (node (ref "U4") (pin "8") (pinfunction "S6_8") (pintype "bidirectional"))
    )
    (net (code "26") (name "MCU_ECHO7") (class "Default")
      (node (ref "U$3") (pin "7") (pinfunction "P3.3_7") (pintype "power_in"))
      (node (ref "U4") (pin "9") (pinfunction "S7_9") (pintype "bidirectional"))
    )
    (net (code "27") (name "MCU_ECHO8") (class "Default")
      (node (ref "U$3") (pin "6") (pinfunction "P3.2_6") (pintype "power_in"))
      (node (ref "U4") (pin "10") (pinfunction "S8_10") (pintype "bidirectional"))
    )
    (net (code "28") (name "MCU_ECHO9") (class "Default")
      (node (ref "U$3") (pin "5") (pinfunction "P3.1_5") (pintype "power_in"))
      (node (ref "U4") (pin "11") (pinfunction "S9_11") (pintype "bidirectional"))
    )
    (net (code "29") (name "MCU_ECHO10") (class "Default")
      (node (ref "U$3") (pin "4") (pinfunction "P3.0_4") (pintype "power_in"))
      (node (ref "U4") (pin "12") (pinfunction "S10_12") (pintype "bidirectional"))
    )
    (net (code "30") (name "Net-(3.3V-PadA)") (class "Default")
      (node (ref "3.3V") (pin "A") (pinfunction "A_A") (pintype "passive"))
      (node (ref "R2") (pin "1") (pinfunction "1_1") (pintype "passive"))
    )
    (net (code "31") (name "Net-(5V-PadA)") (class "Default")
      (node (ref "5V") (pin "A") (pinfunction "A_A") (pintype "passive"))
      (node (ref "R28") (pin "1") (pinfunction "1_1") (pintype "passive"))
    )
    (net (code "32") (name "Net-(C1-Pad1)") (class "Default")
      (node (ref "C1") (pin "1") (pinfunction "1_1") (pintype "passive"))
      (node (ref "R1") (pin "1") (pinfunction "1_1") (pintype "passive"))
      (node (ref "U$1") (pin "P9.5") (pinfunction "VDD_5V_P9.5") (pintype "bidirectional"))
      (node (ref "U$1") (pin "P9.6") (pinfunction "VDD_5V_P9.6") (pintype "bidirectional"))
    )
    (net (code "33") (name "Net-(IN_POWER-PadA)") (class "Default")
      (node (ref "IN_POWER") (pin "A") (pinfunction "A_A") (pintype "passive"))
      (node (ref "R29") (pin "1") (pinfunction "1_1") (pintype "passive"))
    )
    (net (code "34") (name "Net-(J12-Pad1)") (class "Default")
      (node (ref "J12") (pin "1") (pinfunction "1_1") (pintype "passive"))
      (node (ref "R9") (pin "1") (pinfunction "1_1") (pintype "passive"))
    )
    (net (code "35") (name "Net-(J12-Pad12)") (class "Default")
      (node (ref "J12") (pin "12") (pinfunction "12_12") (pintype "passive"))
      (node (ref "R8") (pin "1") (pinfunction "1_1") (pintype "passive"))
    )
    (net (code "36") (name "Net-(POWER_INA-S)") (class "Default")
      (node (ref "D1") (pin "A") (pinfunction "A_A") (pintype "passive"))
      (node (ref "POWER_IN") (pin "1") (pinfunction "S_1") (pintype "passive"))
    )
    (net (code "37") (name "Net-(U1-DREF)") (class "Default")
      (node (ref "C11") (pin "1") (pinfunction "1_1") (pintype "passive"))
      (node (ref "R6") (pin "1") (pinfunction "1_1") (pintype "passive"))
      (node (ref "U1") (pin "23") (pinfunction "DREF_23") (pintype "power_in"))
      (node (ref "U1") (pin "24") (pinfunction "GREF_24") (pintype "input"))
    )
    (net (code "38") (name "Net-(U2-PG)") (class "Default")
      (node (ref "R3") (pin "2") (pinfunction "2_2") (pintype "passive"))
      (node (ref "U2") (pin "4") (pinfunction "PG_4") (pintype "passive"))
    )
    (net (code "39") (name "Net-(U2-SS_TR)") (class "Default")
      (node (ref "C25") (pin "1") (pinfunction "1_1") (pintype "passive"))
      (node (ref "U2") (pin "9") (pinfunction "SS_TR_9") (pintype "passive"))
    )
    (net (code "40") (name "Net-(U2-SW_2)") (class "Default")
      (node (ref "L1") (pin "1") (pinfunction "1_1") (pintype "passive"))
      (node (ref "U2") (pin "1") (pinfunction "SW_2_1") (pintype "passive"))
    )
    (net (code "41") (name "Net-(U3-PG)") (class "Default")
      (node (ref "R4") (pin "2") (pinfunction "2_2") (pintype "passive"))
      (node (ref "U3") (pin "4") (pinfunction "PG_4") (pintype "passive"))
    )
    (net (code "42") (name "Net-(U3-SS_TR)") (class "Default")
      (node (ref "C33") (pin "1") (pinfunction "1_1") (pintype "passive"))
      (node (ref "U3") (pin "9") (pinfunction "SS_TR_9") (pintype "passive"))
    )
    (net (code "43") (name "Net-(U3-SW_2)") (class "Default")
      (node (ref "L2") (pin "1") (pinfunction "1_1") (pintype "passive"))
      (node (ref "U3") (pin "1") (pinfunction "SW_2_1") (pintype "passive"))
    )
    (net (code "44") (name "Net-(U4-DREF)") (class "Default")
      (node (ref "C10") (pin "1") (pinfunction "1_1") (pintype "passive"))
      (node (ref "R5") (pin "1") (pinfunction "1_1") (pintype "passive"))
      (node (ref "U4") (pin "23") (pinfunction "DREF_23") (pintype "power_in"))
      (node (ref "U4") (pin "24") (pinfunction "GREF_24") (pintype "input"))
    )
    (net (code "45") (name "N{slash}A") (class "Default")
      (node (ref "U$5") (pin "7") (pinfunction "NSLEEP_7") (pintype "bidirectional"))
    )
    (net (code "46") (name "P4.6") (class "Default")
      (node (ref "U$3") (pin "35") (pinfunction "P4.6_35") (pintype "power_in"))
    )
    (net (code "47") (name "PWM_C1") (class "Default")
      (node (ref "R12") (pin "2") (pinfunction "2_2") (pintype "passive"))
      (node (ref "U$3") (pin "1") (pinfunction "P1.0_1") (pintype "power_in"))
      (node (ref "U1") (pin "3") (pinfunction "S1_3") (pintype "bidirectional"))
    )
    (net (code "48") (name "PWM_C2") (class "Default")
      (node (ref "R13") (pin "2") (pinfunction "2_2") (pintype "passive"))
      (node (ref "U$3") (pin "2") (pinfunction "P1.1_2") (pintype "power_in"))
      (node (ref "U1") (pin "4") (pinfunction "S2_4") (pintype "bidirectional"))
    )
    (net (code "49") (name "PWM_C3") (class "Default")
      (node (ref "R14") (pin "2") (pinfunction "2_2") (pintype "passive"))
      (node (ref "U$3") (pin "30") (pinfunction "P3.7_30") (pintype "power_in"))
      (node (ref "U1") (pin "5") (pinfunction "S3_5") (pintype "bidirectional"))
    )
    (net (code "50") (name "PWM_C4") (class "Default")
      (node (ref "R15") (pin "2") (pinfunction "2_2") (pintype "passive"))
      (node (ref "U$3") (pin "29") (pinfunction "P3.6_29") (pintype "power_in"))
      (node (ref "U1") (pin "6") (pinfunction "S4_6") (pintype "bidirectional"))
    )
    (net (code "51") (name "PWM_C5") (class "Default")
      (node (ref "R16") (pin "2") (pinfunction "2_2") (pintype "passive"))
      (node (ref "U$3") (pin "28") (pinfunction "P3.5_28") (pintype "power_in"))
      (node (ref "U1") (pin "7") (pinfunction "S5_7") (pintype "bidirectional"))
    )
    (net (code "52") (name "PWM_C6") (class "Default")
      (node (ref "R17") (pin "2") (pinfunction "2_2") (pintype "passive"))
      (node (ref "U$3") (pin "27") (pinfunction "P3.4_27") (pintype "power_in"))
      (node (ref "U1") (pin "8") (pinfunction "S6_8") (pintype "bidirectional"))
    )
    (net (code "53") (name "PWM_C7") (class "Default")
      (node (ref "R18") (pin "2") (pinfunction "2_2") (pintype "passive"))
      (node (ref "U$3") (pin "10") (pinfunction "P1.4_10") (pintype "power_in"))
      (node (ref "U1") (pin "9") (pinfunction "S7_9") (pintype "bidirectional"))
    )
    (net (code "54") (name "PWM_C8") (class "Default")
      (node (ref "R19") (pin "2") (pinfunction "2_2") (pintype "passive"))
      (node (ref "U$3") (pin "11") (pinfunction "P1.5_11") (pintype "power_in"))
      (node (ref "U1") (pin "10") (pinfunction "S8_10") (pintype "bidirectional"))
    )
    (net (code "55") (name "PWM_IN_1") (class "Default")
      (node (ref "IN1") (pin "1") (pinfunction "1_1") (pintype "passive"))
      (node (ref "R20") (pin "1") (pinfunction "1_1") (pintype "passive"))
      (node (ref "U1") (pin "22") (pinfunction "D1_22") (pintype "bidirectional"))
    )
    (net (code "56") (name "PWM_IN_2") (class "Default")
      (node (ref "IN2") (pin "1") (pinfunction "1_1") (pintype "passive"))
      (node (ref "R21") (pin "1") (pinfunction "1_1") (pintype "passive"))
      (node (ref "U1") (pin "21") (pinfunction "D2_21") (pintype "bidirectional"))
    )
    (net (code "57") (name "PWM_IN_3") (class "Default")
      (node (ref "IN3") (pin "1") (pinfunction "1_1") (pintype "passive"))
      (node (ref "R22") (pin "1") (pinfunction "1_1") (pintype "passive"))
      (node (ref "U1") (pin "20") (pinfunction "D3_20") (pintype "bidirectional"))
    )
    (net (code "58") (name "PWM_IN_4") (class "Default")
      (node (ref "IN4") (pin "1") (pinfunction "1_1") (pintype "passive"))
      (node (ref "R23") (pin "1") (pinfunction "1_1") (pintype "passive"))
      (node (ref "U1") (pin "19") (pinfunction "D4_19") (pintype "bidirectional"))
    )
    (net (code "59") (name "PWM_OUT_1") (class "Default")
      (node (ref "OUT1") (pin "1") (pinfunction "1_1") (pintype "passive"))
      (node (ref "R24") (pin "1") (pinfunction "1_1") (pintype "passive"))
      (node (ref "U1") (pin "18") (pinfunction "D5_18") (pintype "bidirectional"))
    )
    (net (code "60") (name "PWM_OUT_2") (class "Default")
      (node (ref "OUT2") (pin "1") (pinfunction "1_1") (pintype "passive"))
      (node (ref "R25") (pin "1") (pinfunction "1_1") (pintype "passive"))
      (node (ref "U1") (pin "17") (pinfunction "D6_17") (pintype "bidirectional"))
    )
    (net (code "61") (name "PWM_OUT_3") (class "Default")
      (node (ref "OUT3") (pin "1") (pinfunction "1_1") (pintype "passive"))
      (node (ref "R26") (pin "1") (pinfunction "1_1") (pintype "passive"))
      (node (ref "U1") (pin "16") (pinfunction "D7_16") (pintype "bidirectional"))
    )
    (net (code "62") (name "PWM_OUT_4") (class "Default")
      (node (ref "OUT4") (pin "1") (pinfunction "1_1") (pintype "passive"))
      (node (ref "R27") (pin "1") (pinfunction "1_1") (pintype "passive"))
      (node (ref "U1") (pin "15") (pinfunction "D8_15") (pintype "bidirectional"))
    )
    (net (code "63") (name "RESET") (class "Default")
      (node (ref "C16") (pin "1") (pinfunction "1_1") (pintype "passive"))
      (node (ref "C34") (pin "1") (pinfunction "1_1") (pintype "passive"))
      (node (ref "R7") (pin "1") (pinfunction "1_1") (pintype "passive"))
      (node (ref "R8") (pin "2") (pinfunction "2_2") (pintype "passive"))
      (node (ref "RESET") (pin "B") (pinfunction "S_B") (pintype "passive"))
      (node (ref "RESET") (pin "B'") (pinfunction "S1_B'") (pintype "passive"))
      (node (ref "U$3") (pin "23") (pinfunction "RST_23") (pintype "power_in"))
    )
    (net (code "64") (name "SCL") (class "Default")
      (node (ref "U$1") (pin "P9.19") (pinfunction "I2C2_SCL_P9.19") (pintype "bidirectional"))
      (node (ref "U$4") (pin "1") (pinfunction "A_1_1") (pintype "bidirectional"))
    )
    (net (code "65") (name "SDA") (class "Default")
      (node (ref "U$1") (pin "P9.20") (pinfunction "I2C2_SDA_P9.20") (pintype "bidirectional"))
      (node (ref "U$4") (pin "4") (pinfunction "A_2_4") (pintype "bidirectional"))
    )
    (net (code "66") (name "SIMO") (class "Default")
      (node (ref "U$1") (pin "P9.30") (pinfunction "GPIO_122_P9.30") (pintype "bidirectional"))
      (node (ref "U$4") (pin "6") (pinfunction "B_2_6") (pintype "bidirectional"))
    )
    (net (code "67") (name "SIMO{slash}SDA") (class "Default")
      (node (ref "R11") (pin "1") (pinfunction "1_1") (pintype "passive"))
      (node (ref "U$3") (pin "31") (pinfunction "P1.6_31") (pintype "power_in"))
      (node (ref "U$4") (pin "5") (pinfunction "C_2_5") (pintype "bidirectional"))
    )
    (net (code "68") (name "SOMI") (class "Default")
      (node (ref "U$1") (pin "P9.29") (pinfunction "GPIO_121_P9.29") (pintype "bidirectional"))
      (node (ref "U$4") (pin "3") (pinfunction "B_1_3") (pintype "bidirectional"))
    )
    (net (code "69") (name "SOMI{slash}SCL") (class "Default")
      (node (ref "R10") (pin "1") (pinfunction "1_1") (pintype "passive"))
      (node (ref "U$3") (pin "32") (pinfunction "P1.7_32") (pintype "power_in"))
      (node (ref "U$4") (pin "2") (pinfunction "C_1_2") (pintype "bidirectional"))
    )
    (net (code "70") (name "SPI_CLK") (class "Default")
      (node (ref "U$1") (pin "P9.31") (pinfunction "GPIO_120_P9.31") (pintype "bidirectional"))
      (node (ref "U$3") (pin "26") (pinfunction "P2.2_26") (pintype "power_in"))
    )
    (net (code "71") (name "SPI_SL") (class "Default")
      (node (ref "SPDT") (pin "2") (pinfunction "C1_2") (pintype "bidirectional"))
      (node (ref "U$3") (pin "9") (pinfunction "P1.3_9") (pintype "power_in"))
    )
    (net (code "72") (name "SPI_SL0") (class "Default")
      (node (ref "SPDT") (pin "1") (pinfunction "A1_1") (pintype "bidirectional"))
      (node (ref "U$1") (pin "P9.28") (pinfunction "GPIO_123_P9.28") (pintype "bidirectional"))
    )
    (net (code "73") (name "SPI_SL1") (class "Default")
      (node (ref "SPDT") (pin "3") (pinfunction "B1_3") (pintype "bidirectional"))
      (node (ref "U$1") (pin "P9.42") (pinfunction "GPIO_7_P9.42") (pintype "bidirectional"))
    )
    (net (code "74") (name "TCK") (class "Default")
      (node (ref "J12") (pin "8") (pinfunction "8_8") (pintype "passive"))
      (node (ref "U$3") (pin "15") (pinfunction "PJ.3_15") (pintype "power_in"))
    )
    (net (code "75") (name "TDI") (class "Default")
      (node (ref "J12") (pin "4") (pinfunction "4_4") (pintype "passive"))
      (node (ref "U$3") (pin "13") (pinfunction "PJ.1_13") (pintype "power_in"))
    )
    (net (code "76") (name "TDO") (class "Default")
      (node (ref "J12") (pin "2") (pinfunction "2_2") (pintype "passive"))
      (node (ref "U$3") (pin "12") (pinfunction "PJ.0_12") (pintype "power_in"))
    )
    (net (code "77") (name "TEST") (class "Default")
      (node (ref "J12") (pin "7") (pinfunction "7_7") (pintype "passive"))
      (node (ref "U$3") (pin "22") (pinfunction "TEST_22") (pintype "power_in"))
    )
    (net (code "78") (name "TMS") (class "Default")
      (node (ref "J12") (pin "6") (pinfunction "6_6") (pintype "passive"))
      (node (ref "U$3") (pin "14") (pinfunction "PJ.2_14") (pintype "power_in"))
    )
    (net (code "79") (name "TRIG_1") (class "Default")
      (node (ref "J1") (pin "2") (pinfunction "2_2") (pintype "passive"))
      (node (ref "U$3") (pin "21") (pinfunction "P2.6_21") (pintype "power_in"))
    )
    (net (code "80") (name "TRIG_2") (class "Default")
      (node (ref "J1") (pin "6") (pinfunction "6_6") (pintype "passive"))
      (node (ref "U$3") (pin "24") (pinfunction "P2.0_24") (pintype "power_in"))
    )
    (net (code "81") (name "TRIG_3") (class "Default")
      (node (ref "J1") (pin "10") (pinfunction "10_10") (pintype "passive"))
      (node (ref "U$3") (pin "25") (pinfunction "P2.1_25") (pintype "power_in"))
    )
    (net (code "82") (name "TRIG_4") (class "Default")
      (node (ref "J1") (pin "14") (pinfunction "14_14") (pintype "passive"))
      (node (ref "U$3") (pin "33") (pinfunction "P4.4_33") (pintype "power_in"))
    )
    (net (code "83") (name "TRIG_5") (class "Default")
      (node (ref "J1") (pin "18") (pinfunction "18_18") (pintype "passive"))
      (node (ref "U$3") (pin "34") (pinfunction "P4.5_34") (pintype "power_in"))
    )
    (net (code "84") (name "TRIG_6") (class "Default")
      (node (ref "J2") (pin "2") (pinfunction "2_2") (pintype "passive"))
      (node (ref "U$3") (pin "42") (pinfunction "PJ.6_42") (pintype "power_in"))
    )
    (net (code "85") (name "TRIG_7") (class "Default")
      (node (ref "J2") (pin "6") (pinfunction "6_6") (pintype "passive"))
      (node (ref "U$3") (pin "43") (pinfunction "PJ.7_43") (pintype "power_in"))
    )
    (net (code "86") (name "TRIG_8") (class "Default")
      (node (ref "J2") (pin "10") (pinfunction "10_10") (pintype "passive"))
      (node (ref "U$3") (pin "45") (pinfunction "PJ.4_45") (pintype "power_in"))
    )
    (net (code "87") (name "TRIG_9") (class "Default")
      (node (ref "J2") (pin "14") (pinfunction "14_14") (pintype "passive"))
      (node (ref "U$3") (pin "46") (pinfunction "PJ.5_46") (pintype "power_in"))
    )
    (net (code "88") (name "TRIG_10") (class "Default")
      (node (ref "J2") (pin "18") (pinfunction "18_18") (pintype "passive"))
      (node (ref "U$3") (pin "3") (pinfunction "P1.2_3") (pintype "power_in"))
    )
    (net (code "89") (name "VCC") (class "Default")
      (node (ref "C22") (pin "1") (pinfunction "1_1") (pintype "passive"))
      (node (ref "C23") (pin "1") (pinfunction "1_1") (pintype "passive"))
      (node (ref "C24") (pin "1") (pinfunction "1_1") (pintype "passive"))
      (node (ref "C29") (pin "1") (pinfunction "1_1") (pintype "passive"))
      (node (ref "C30") (pin "1") (pinfunction "1_1") (pintype "passive"))
      (node (ref "C31") (pin "1") (pinfunction "1_1") (pintype "passive"))
      (node (ref "C32") (pin "1") (pinfunction "1_1") (pintype "passive"))
      (node (ref "C35") (pin "1") (pinfunction "1_1") (pintype "passive"))
      (node (ref "C36") (pin "1") (pinfunction "1_1") (pintype "passive"))
      (node (ref "C37") (pin "A") (pinfunction "+_A") (pintype "passive"))
      (node (ref "D1") (pin "C") (pinfunction "C_C") (pintype "passive"))
      (node (ref "R29") (pin "2") (pinfunction "2_2") (pintype "passive"))
      (node (ref "U2") (pin "10") (pinfunction "AVIN_10") (pintype "passive"))
      (node (ref "U2") (pin "11") (pinfunction "PVIN_2_11") (pintype "passive"))
      (node (ref "U2") (pin "13") (pinfunction "EN_13") (pintype "passive"))
      (node (ref "U3") (pin "10") (pinfunction "AVIN_10") (pintype "passive"))
      (node (ref "U3") (pin "11") (pinfunction "PVIN_2_11") (pintype "passive"))
      (node (ref "U3") (pin "13") (pinfunction "EN_13") (pintype "passive"))
    )
    (net (code "90") (name "unconnected-(J12-Pad3)") (class "Default")
      (node (ref "J12") (pin "3") (pinfunction "3_3") (pintype "passive"))
    )
    (net (code "91") (name "unconnected-(J12-Pad5)") (class "Default")
      (node (ref "J12") (pin "5") (pinfunction "5_5") (pintype "passive"))
    )
    (net (code "92") (name "unconnected-(J12-Pad9)") (class "Default")
      (node (ref "J12") (pin "9") (pinfunction "9_9") (pintype "passive"))
    )
    (net (code "93") (name "unconnected-(J12-Pad11)") (class "Default")
      (node (ref "J12") (pin "11") (pinfunction "11_11") (pintype "passive"))
    )
    (net (code "94") (name "unconnected-(J12-Pad13)") (class "Default")
      (node (ref "J12") (pin "13") (pinfunction "13_13") (pintype "passive"))
    )
    (net (code "95") (name "unconnected-(J12-Pad14)") (class "Default")
      (node (ref "J12") (pin "14") (pinfunction "14_14") (pintype "passive"))
    )
    (net (code "96") (name "unconnected-(U$1A-GPIO_8-PadP8.35)") (class "Default")
      (node (ref "U$1") (pin "P8.35") (pinfunction "GPIO_8_P8.35") (pintype "bidirectional"))
    )
    (net (code "97") (name "unconnected-(U$1A-GPIO_9-PadP8.33)") (class "Default")
      (node (ref "U$1") (pin "P8.33") (pinfunction "GPIO_9_P8.33") (pintype "bidirectional"))
    )
    (net (code "98") (name "unconnected-(U$1A-GPIO_10-PadP8.31)") (class "Default")
      (node (ref "U$1") (pin "P8.31") (pinfunction "GPIO_10_P8.31") (pintype "bidirectional"))
    )
    (net (code "99") (name "unconnected-(U$1A-GPIO_11-PadP8.32)") (class "Default")
      (node (ref "U$1") (pin "P8.32") (pinfunction "GPIO_11_P8.32") (pintype "bidirectional"))
    )
    (net (code "100") (name "unconnected-(U$1A-GPIO_22-PadP8.19)") (class "Default")
      (node (ref "U$1") (pin "P8.19") (pinfunction "GPIO_22_P8.19") (pintype "bidirectional"))
    )
    (net (code "101") (name "unconnected-(U$1A-GPIO_23-PadP8.13)") (class "Default")
      (node (ref "U$1") (pin "P8.13") (pinfunction "GPIO_23_P8.13") (pintype "bidirectional"))
    )
    (net (code "102") (name "unconnected-(U$1A-GPIO_26-PadP8.14)") (class "Default")
      (node (ref "U$1") (pin "P8.14") (pinfunction "GPIO_26_P8.14") (pintype "bidirectional"))
    )
    (net (code "103") (name "unconnected-(U$1A-GPIO_27-PadP8.17)") (class "Default")
      (node (ref "U$1") (pin "P8.17") (pinfunction "GPIO_27_P8.17") (pintype "bidirectional"))
    )
    (net (code "104") (name "unconnected-(U$1A-GPIO_32-PadP8.25)") (class "Default")
      (node (ref "U$1") (pin "P8.25") (pinfunction "GPIO_32_P8.25") (pintype "bidirectional"))
    )
    (net (code "105") (name "unconnected-(U$1A-GPIO_33-PadP8.24)") (class "Default")
      (node (ref "U$1") (pin "P8.24") (pinfunction "GPIO_33_P8.24") (pintype "bidirectional"))
    )
    (net (code "106") (name "unconnected-(U$1A-GPIO_34-PadP8.5)") (class "Default")
      (node (ref "U$1") (pin "P8.5") (pinfunction "GPIO_34_P8.5") (pintype "bidirectional"))
    )
    (net (code "107") (name "unconnected-(U$1A-GPIO_35-PadP8.6)") (class "Default")
      (node (ref "U$1") (pin "P8.6") (pinfunction "GPIO_35_P8.6") (pintype "bidirectional"))
    )
    (net (code "108") (name "unconnected-(U$1A-GPIO_36-PadP8.23)") (class "Default")
      (node (ref "U$1") (pin "P8.23") (pinfunction "GPIO_36_P8.23") (pintype "bidirectional"))
    )
    (net (code "109") (name "unconnected-(U$1A-GPIO_37-PadP8.22)") (class "Default")
      (node (ref "U$1") (pin "P8.22") (pinfunction "GPIO_37_P8.22") (pintype "bidirectional"))
    )
    (net (code "110") (name "unconnected-(U$1A-GPIO_38-PadP8.3)") (class "Default")
      (node (ref "U$1") (pin "P8.3") (pinfunction "GPIO_38_P8.3") (pintype "bidirectional"))
    )
    (net (code "111") (name "unconnected-(U$1A-GPIO_39-PadP8.4)") (class "Default")
      (node (ref "U$1") (pin "P8.4") (pinfunction "GPIO_39_P8.4") (pintype "bidirectional"))
    )
    (net (code "112") (name "unconnected-(U$1A-GPIO_44-PadP8.12)") (class "Default")
      (node (ref "U$1") (pin "P8.12") (pinfunction "GPIO_44_P8.12") (pintype "bidirectional"))
    )
    (net (code "113") (name "unconnected-(U$1A-GPIO_45-PadP8.11)") (class "Default")
      (node (ref "U$1") (pin "P8.11") (pinfunction "GPIO_45_P8.11") (pintype "bidirectional"))
    )
    (net (code "114") (name "unconnected-(U$1A-GPIO_46-PadP8.16)") (class "Default")
      (node (ref "U$1") (pin "P8.16") (pinfunction "GPIO_46_P8.16") (pintype "bidirectional"))
    )
    (net (code "115") (name "unconnected-(U$1A-GPIO_47-PadP8.15)") (class "Default")
      (node (ref "U$1") (pin "P8.15") (pinfunction "GPIO_47_P8.15") (pintype "bidirectional"))
    )
    (net (code "116") (name "unconnected-(U$1A-GPIO_61-PadP8.26)") (class "Default")
      (node (ref "U$1") (pin "P8.26") (pinfunction "GPIO_61_P8.26") (pintype "bidirectional"))
    )
    (net (code "117") (name "unconnected-(U$1A-GPIO_62-PadP8.21)") (class "Default")
      (node (ref "U$1") (pin "P8.21") (pinfunction "GPIO_62_P8.21") (pintype "bidirectional"))
    )
    (net (code "118") (name "unconnected-(U$1A-GPIO_63-PadP8.20)") (class "Default")
      (node (ref "U$1") (pin "P8.20") (pinfunction "GPIO_63_P8.20") (pintype "bidirectional"))
    )
    (net (code "119") (name "unconnected-(U$1A-GPIO_65-PadP8.18)") (class "Default")
      (node (ref "U$1") (pin "P8.18") (pinfunction "GPIO_65_P8.18") (pintype "bidirectional"))
    )
    (net (code "120") (name "unconnected-(U$1A-GPIO_66-PadP8.7)") (class "Default")
      (node (ref "U$1") (pin "P8.7") (pinfunction "GPIO_66_P8.7") (pintype "bidirectional"))
    )
    (net (code "121") (name "unconnected-(U$1A-GPIO_67-PadP8.8)") (class "Default")
      (node (ref "U$1") (pin "P8.8") (pinfunction "GPIO_67_P8.8") (pintype "bidirectional"))
    )
    (net (code "122") (name "unconnected-(U$1A-GPIO_68-PadP8.10)") (class "Default")
      (node (ref "U$1") (pin "P8.10") (pinfunction "GPIO_68_P8.10") (pintype "bidirectional"))
    )
    (net (code "123") (name "unconnected-(U$1A-GPIO_69-PadP8.9)") (class "Default")
      (node (ref "U$1") (pin "P8.9") (pinfunction "GPIO_69_P8.9") (pintype "bidirectional"))
    )
    (net (code "124") (name "unconnected-(U$1A-GPIO_70-PadP8.45)") (class "Default")
      (node (ref "U$1") (pin "P8.45") (pinfunction "GPIO_70_P8.45") (pintype "bidirectional"))
    )
    (net (code "125") (name "unconnected-(U$1A-GPIO_71-PadP8.46)") (class "Default")
      (node (ref "U$1") (pin "P8.46") (pinfunction "GPIO_71_P8.46") (pintype "bidirectional"))
    )
    (net (code "126") (name "unconnected-(U$1A-GPIO_72-PadP8.43)") (class "Default")
      (node (ref "U$1") (pin "P8.43") (pinfunction "GPIO_72_P8.43") (pintype "bidirectional"))
    )
    (net (code "127") (name "unconnected-(U$1A-GPIO_73-PadP8.44)") (class "Default")
      (node (ref "U$1") (pin "P8.44") (pinfunction "GPIO_73_P8.44") (pintype "bidirectional"))
    )
    (net (code "128") (name "unconnected-(U$1A-GPIO_74-PadP8.41)") (class "Default")
      (node (ref "U$1") (pin "P8.41") (pinfunction "GPIO_74_P8.41") (pintype "bidirectional"))
    )
    (net (code "129") (name "unconnected-(U$1A-GPIO_75-PadP8.42)") (class "Default")
      (node (ref "U$1") (pin "P8.42") (pinfunction "GPIO_75_P8.42") (pintype "bidirectional"))
    )
    (net (code "130") (name "unconnected-(U$1A-GPIO_76-PadP8.39)") (class "Default")
      (node (ref "U$1") (pin "P8.39") (pinfunction "GPIO_76_P8.39") (pintype "bidirectional"))
    )
    (net (code "131") (name "unconnected-(U$1A-GPIO_77-PadP8.40)") (class "Default")
      (node (ref "U$1") (pin "P8.40") (pinfunction "GPIO_77_P8.40") (pintype "bidirectional"))
    )
    (net (code "132") (name "unconnected-(U$1A-GPIO_78-PadP8.37)") (class "Default")
      (node (ref "U$1") (pin "P8.37") (pinfunction "GPIO_78_P8.37") (pintype "bidirectional"))
    )
    (net (code "133") (name "unconnected-(U$1A-GPIO_79-PadP8.38)") (class "Default")
      (node (ref "U$1") (pin "P8.38") (pinfunction "GPIO_79_P8.38") (pintype "bidirectional"))
    )
    (net (code "134") (name "unconnected-(U$1A-GPIO_80-PadP8.36)") (class "Default")
      (node (ref "U$1") (pin "P8.36") (pinfunction "GPIO_80_P8.36") (pintype "bidirectional"))
    )
    (net (code "135") (name "unconnected-(U$1A-GPIO_81-PadP8.34)") (class "Default")
      (node (ref "U$1") (pin "P8.34") (pinfunction "GPIO_81_P8.34") (pintype "bidirectional"))
    )
    (net (code "136") (name "unconnected-(U$1A-GPIO_86-PadP8.27)") (class "Default")
      (node (ref "U$1") (pin "P8.27") (pinfunction "GPIO_86_P8.27") (pintype "bidirectional"))
    )
    (net (code "137") (name "unconnected-(U$1A-GPIO_87-PadP8.29)") (class "Default")
      (node (ref "U$1") (pin "P8.29") (pinfunction "GPIO_87_P8.29") (pintype "bidirectional"))
    )
    (net (code "138") (name "unconnected-(U$1A-GPIO_88-PadP8.28)") (class "Default")
      (node (ref "U$1") (pin "P8.28") (pinfunction "GPIO_88_P8.28") (pintype "bidirectional"))
    )
    (net (code "139") (name "unconnected-(U$1A-GPIO_89-PadP8.30)") (class "Default")
      (node (ref "U$1") (pin "P8.30") (pinfunction "GPIO_89_P8.30") (pintype "bidirectional"))
    )
    (net (code "140") (name "unconnected-(U$1B-AIN0-PadP9.39)") (class "Default")
      (node (ref "U$1") (pin "P9.39") (pinfunction "AIN0_P9.39") (pintype "bidirectional"))
    )
    (net (code "141") (name "unconnected-(U$1B-AIN1-PadP9.40)") (class "Default")
      (node (ref "U$1") (pin "P9.40") (pinfunction "AIN1_P9.40") (pintype "bidirectional"))
    )
    (net (code "142") (name "unconnected-(U$1B-AIN2-PadP9.37)") (class "Default")
      (node (ref "U$1") (pin "P9.37") (pinfunction "AIN2_P9.37") (pintype "bidirectional"))
    )
    (net (code "143") (name "unconnected-(U$1B-AIN3-PadP9.38)") (class "Default")
      (node (ref "U$1") (pin "P9.38") (pinfunction "AIN3_P9.38") (pintype "bidirectional"))
    )
    (net (code "144") (name "unconnected-(U$1B-AIN4-PadP9.33)") (class "Default")
      (node (ref "U$1") (pin "P9.33") (pinfunction "AIN4_P9.33") (pintype "bidirectional"))
    )
    (net (code "145") (name "unconnected-(U$1B-AIN5-PadP9.36)") (class "Default")
      (node (ref "U$1") (pin "P9.36") (pinfunction "AIN5_P9.36") (pintype "bidirectional"))
    )
    (net (code "146") (name "unconnected-(U$1B-AIN6-PadP9.35)") (class "Default")
      (node (ref "U$1") (pin "P9.35") (pinfunction "AIN6_P9.35") (pintype "bidirectional"))
    )
    (net (code "147") (name "unconnected-(U$1B-DGND-PadP9.43)") (class "Default")
      (node (ref "U$1") (pin "P9.43") (pinfunction "DGND_P9.43") (pintype "bidirectional"))
    )
    (net (code "148") (name "unconnected-(U$1B-DGND-PadP9.44)") (class "Default")
      (node (ref "U$1") (pin "P9.44") (pinfunction "DGND_P9.44") (pintype "bidirectional"))
    )
    (net (code "149") (name "unconnected-(U$1B-DGND-PadP9.45)") (class "Default")
      (node (ref "U$1") (pin "P9.45") (pinfunction "DGND_P9.45") (pintype "bidirectional"))
    )
    (net (code "150") (name "unconnected-(U$1B-DGND-PadP9.46)") (class "Default")
      (node (ref "U$1") (pin "P9.46") (pinfunction "DGND_P9.46") (pintype "bidirectional"))
    )
    (net (code "151") (name "unconnected-(U$1B-GNDA_ADC-PadP9.34)") (class "Default")
      (node (ref "U$1") (pin "P9.34") (pinfunction "GNDA_ADC_P9.34") (pintype "bidirectional"))
    )
    (net (code "152") (name "unconnected-(U$1B-GPIO_3-PadP9.21)") (class "Default")
      (node (ref "U$1") (pin "P9.21") (pinfunction "GPIO_3_P9.21") (pintype "bidirectional"))
    )
    (net (code "153") (name "unconnected-(U$1B-GPIO_4-PadP9.17)") (class "Default")
      (node (ref "U$1") (pin "P9.17") (pinfunction "GPIO_4_P9.17") (pintype "bidirectional"))
    )
    (net (code "154") (name "unconnected-(U$1B-GPIO_5-PadP9.18)") (class "Default")
      (node (ref "U$1") (pin "P9.18") (pinfunction "GPIO_5_P9.18") (pintype "bidirectional"))
    )
    (net (code "155") (name "unconnected-(U$1B-GPIO_20-PadP9.41)") (class "Default")
      (node (ref "U$1") (pin "P9.41") (pinfunction "GPIO_20_P9.41") (pintype "bidirectional"))
    )
    (net (code "156") (name "unconnected-(U$1B-GPIO_30-PadP9.11)") (class "Default")
      (node (ref "U$1") (pin "P9.11") (pinfunction "GPIO_30_P9.11") (pintype "bidirectional"))
    )
    (net (code "157") (name "unconnected-(U$1B-GPIO_31-PadP9.13)") (class "Default")
      (node (ref "U$1") (pin "P9.13") (pinfunction "GPIO_31_P9.13") (pintype "bidirectional"))
    )
    (net (code "158") (name "unconnected-(U$1B-GPIO_40-PadP9.14)") (class "Default")
      (node (ref "U$1") (pin "P9.14") (pinfunction "GPIO_40_P9.14") (pintype "bidirectional"))
    )
    (net (code "159") (name "unconnected-(U$1B-GPIO_48-PadP9.15)") (class "Default")
      (node (ref "U$1") (pin "P9.15") (pinfunction "GPIO_48_P9.15") (pintype "bidirectional"))
    )
    (net (code "160") (name "unconnected-(U$1B-GPIO_51-PadP9.16)") (class "Default")
      (node (ref "U$1") (pin "P9.16") (pinfunction "GPIO_51_P9.16") (pintype "bidirectional"))
    )
    (net (code "161") (name "unconnected-(U$1B-GPIO_60-PadP9.12)") (class "Default")
      (node (ref "U$1") (pin "P9.12") (pinfunction "GPIO_60_P9.12") (pintype "bidirectional"))
    )
    (net (code "162") (name "unconnected-(U$1B-GPIO_117-PadP9.25)") (class "Default")
      (node (ref "U$1") (pin "P9.25") (pinfunction "GPIO_117_P9.25") (pintype "bidirectional"))
    )
    (net (code "163") (name "unconnected-(U$1B-GPIO_125-PadP9.27)") (class "Default")
      (node (ref "U$1") (pin "P9.27") (pinfunction "GPIO_125_P9.27") (pintype "bidirectional"))
    )
    (net (code "164") (name "unconnected-(U$1B-PWR_BUT-PadP9.9)") (class "Default")
      (node (ref "U$1") (pin "P9.9") (pinfunction "PWR_BUT_P9.9") (pintype "bidirectional"))
    )
    (net (code "165") (name "unconnected-(U$1B-SYS_5V-PadP9.7)") (class "Default")
      (node (ref "U$1") (pin "P9.7") (pinfunction "SYS_5V_P9.7") (pintype "bidirectional"))
    )
    (net (code "166") (name "unconnected-(U$1B-SYS_5V-PadP9.8)") (class "Default")
      (node (ref "U$1") (pin "P9.8") (pinfunction "SYS_5V_P9.8") (pintype "bidirectional"))
    )
    (net (code "167") (name "unconnected-(U$1B-SYS_RESET~{N}-PadP9.10)") (class "Default")
      (node (ref "U$1") (pin "P9.10") (pinfunction "SYS_RESET~{N}_P9.10") (pintype "bidirectional"))
    )
    (net (code "168") (name "unconnected-(U$1B-VDD_3V3-PadP9.3)") (class "Default")
      (node (ref "U$1") (pin "P9.3") (pinfunction "VDD_3V3_P9.3") (pintype "bidirectional"))
    )
    (net (code "169") (name "unconnected-(U$1B-VDD_3V3-PadP9.4)") (class "Default")
      (node (ref "U$1") (pin "P9.4") (pinfunction "VDD_3V3_P9.4") (pintype "bidirectional"))
    )
    (net (code "170") (name "unconnected-(U$1B-VDD_ADC-PadP9.32)") (class "Default")
      (node (ref "U$1") (pin "P9.32") (pinfunction "VDD_ADC_P9.32") (pintype "bidirectional"))
    )
    (net (code "171") (name "unconnected-(U$3-P2.3-Pad39)") (class "Default")
      (node (ref "U$3") (pin "39") (pinfunction "P2.3_39") (pintype "power_in"))
    )
    (net (code "172") (name "unconnected-(U$3-P2.4-Pad40)") (class "Default")
      (node (ref "U$3") (pin "40") (pinfunction "P2.4_40") (pintype "power_in"))
    )
    (net (code "173") (name "unconnected-(U$3-P2.7-Pad38)") (class "Default")
      (node (ref "U$3") (pin "38") (pinfunction "P2.7_38") (pintype "power_in"))
    )
    (net (code "174") (name "unconnected-(U$3-T_PAD-Pad49)") (class "Default")
      (node (ref "U$3") (pin "49") (pinfunction "T_PAD_49") (pintype "power_in"))
    )
    (net (code "175") (name "unconnected-(U1-D9-Pad14)") (class "Default")
      (node (ref "U1") (pin "14") (pinfunction "D9_14") (pintype "bidirectional"))
    )
    (net (code "176") (name "unconnected-(U1-D10-Pad13)") (class "Default")
      (node (ref "U1") (pin "13") (pinfunction "D10_13") (pintype "bidirectional"))
    )
    (net (code "177") (name "unconnected-(U1-S9-Pad11)") (class "Default")
      (node (ref "U1") (pin "11") (pinfunction "S9_11") (pintype "bidirectional"))
    )
    (net (code "178") (name "unconnected-(U1-S10-Pad12)") (class "Default")
      (node (ref "U1") (pin "12") (pinfunction "S10_12") (pintype "bidirectional"))
    )
  )
)
